# Ausgangsstufe.net
KiCad netlist of a schematic drawn in Altium Designer
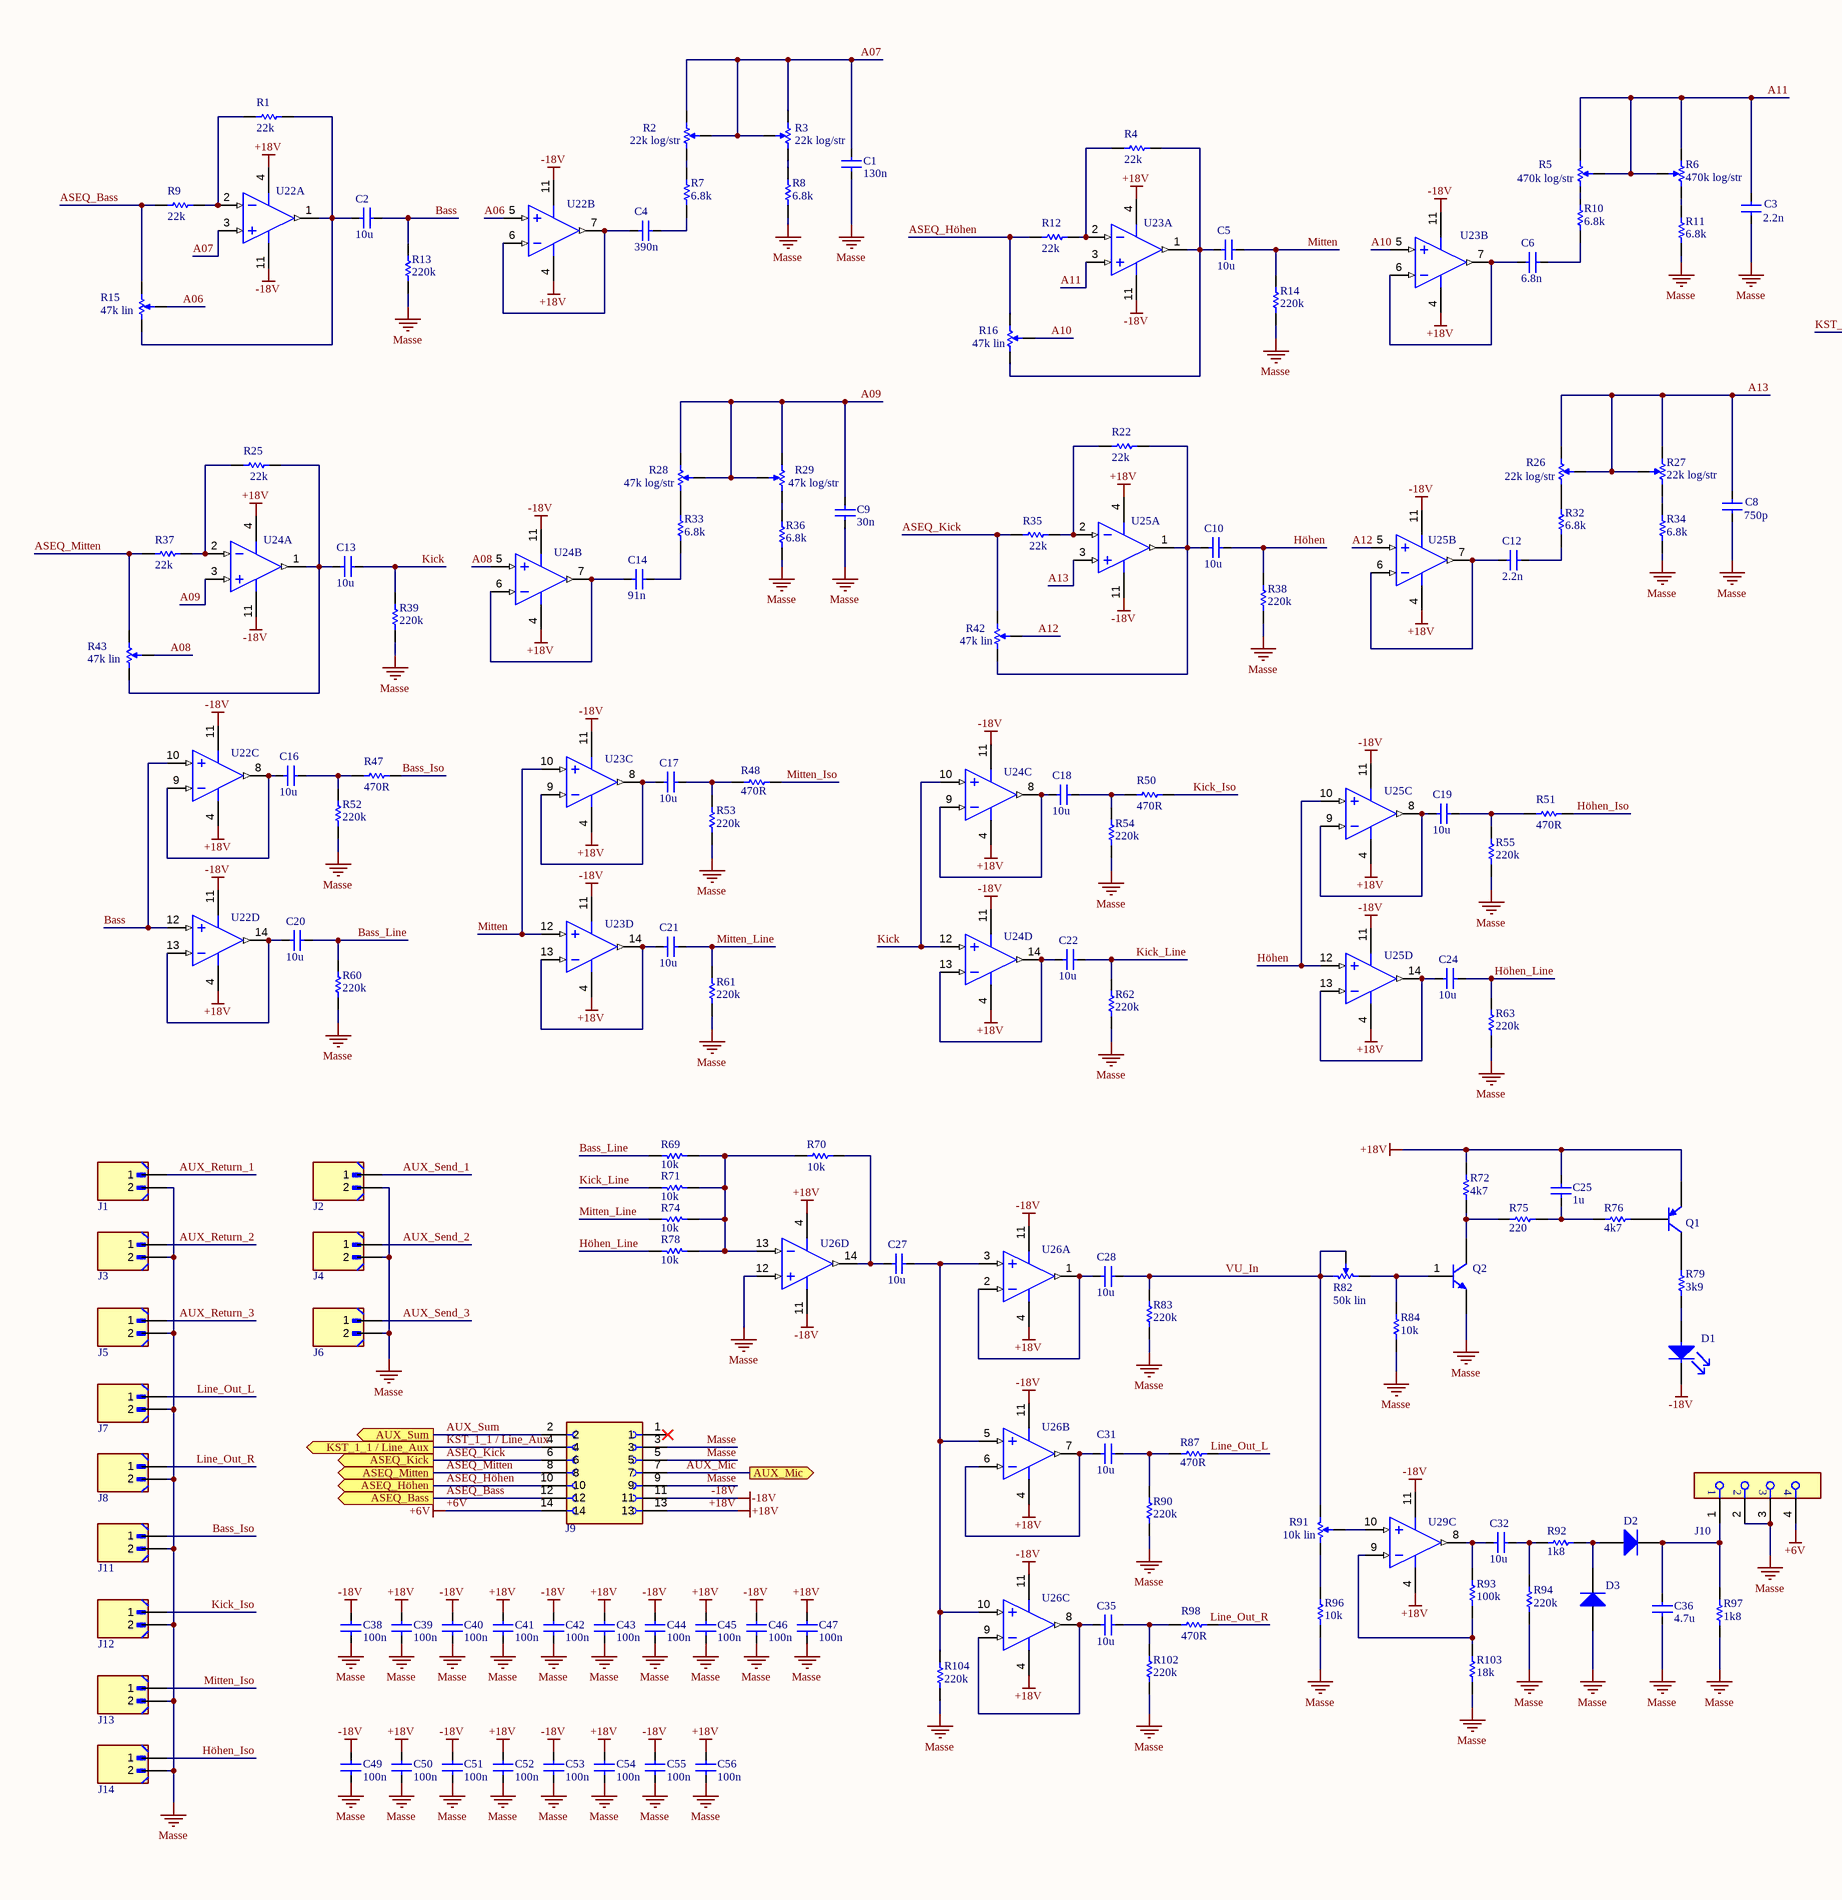
[diagram p0: Ausgangsstufe.SchDoc, left]
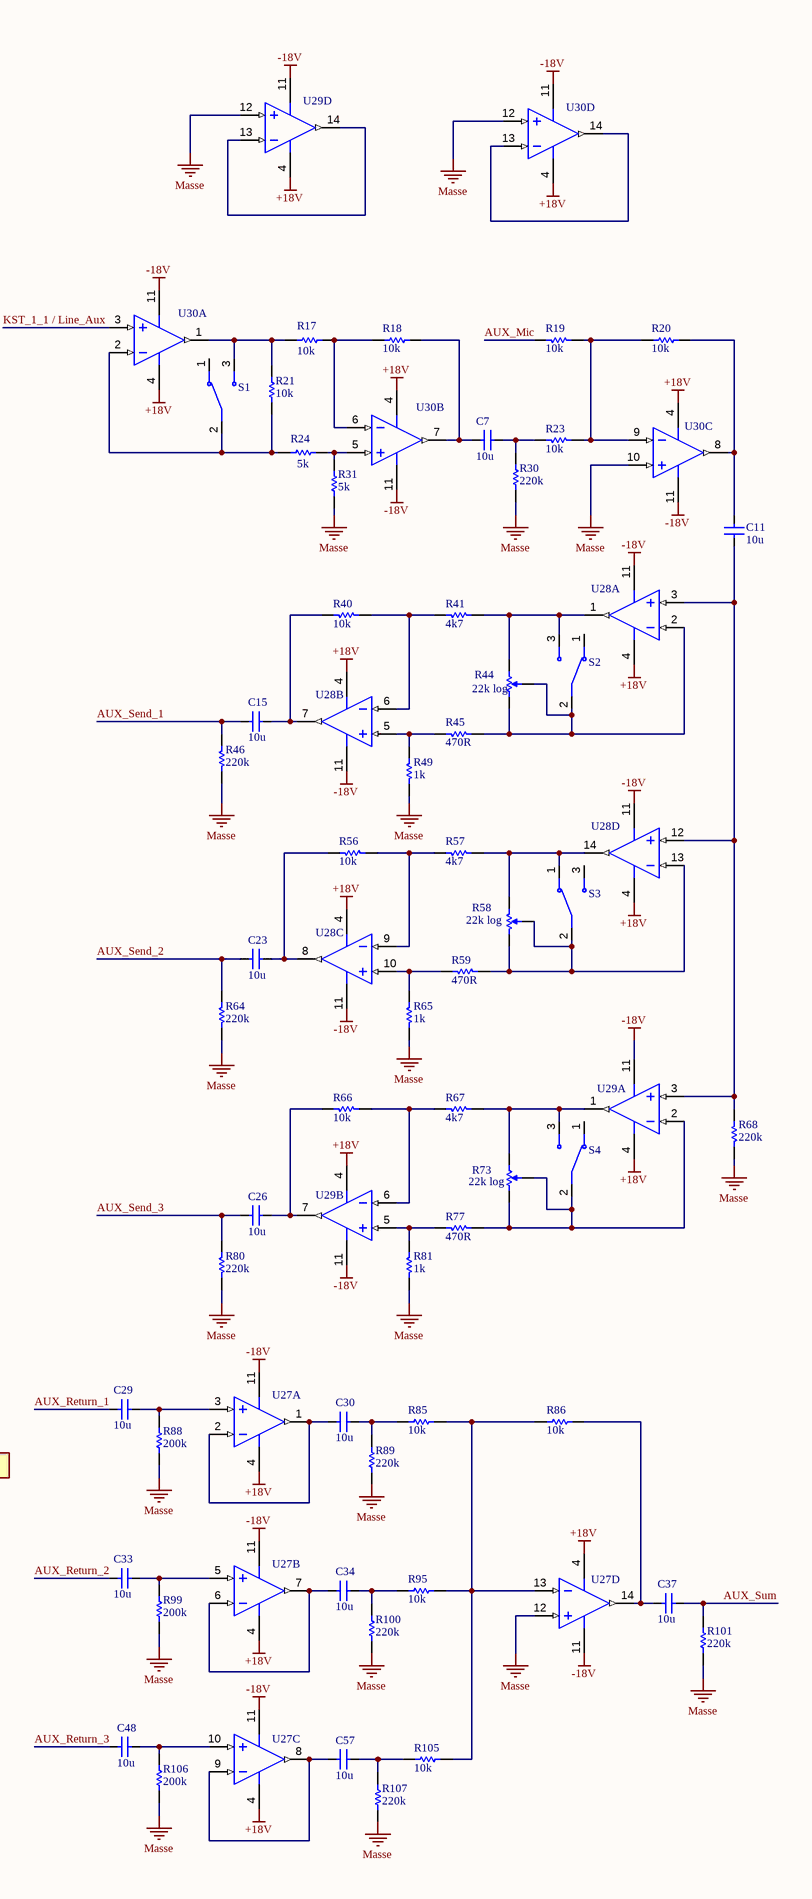
[diagram p1: Ausgangsstufe.SchDoc, right]

(export (version "E")
  (design (tool "Eeschema 10.0.6"))
  (components
    (comp (ref "C1")
      (value "130n")
      (footprint "0805")
      (description "0805 Kondensator")
      (libsource (lib "Bauteile") (part "0805 Kondensator"))
    )
    (comp (ref "C2")
      (value "10u")
      (footprint "0805")
      (description "0805 Kondensator")
      (libsource (lib "Bauteile") (part "0805 Kondensator"))
    )
    (comp (ref "C3")
      (value "2.2n")
      (footprint "0805")
      (description "0805 Kondensator")
      (libsource (lib "Bauteile") (part "0805 Kondensator"))
    )
    (comp (ref "C4")
      (value "390n")
      (footprint "0805")
      (description "0805 Kondensator")
      (libsource (lib "Bauteile") (part "0805 Kondensator"))
    )
    (comp (ref "C5")
      (value "10u")
      (footprint "0805")
      (description "0805 Kondensator")
      (libsource (lib "Bauteile") (part "0805 Kondensator"))
    )
    (comp (ref "C6")
      (value "6.8n")
      (footprint "0805")
      (description "0805 Kondensator")
      (libsource (lib "Bauteile") (part "0805 Kondensator"))
    )
    (comp (ref "C7")
      (value "10u")
      (footprint "0805")
      (description "0805 Kondensator")
      (libsource (lib "Bauteile") (part "0805 Kondensator"))
    )
    (comp (ref "C8")
      (value "750p")
      (footprint "0805")
      (description "0805 Kondensator")
      (libsource (lib "Bauteile") (part "0805 Kondensator"))
    )
    (comp (ref "C9")
      (value "30n")
      (footprint "0805")
      (description "0805 Kondensator")
      (libsource (lib "Bauteile") (part "0805 Kondensator"))
    )
    (comp (ref "C10")
      (value "10u")
      (footprint "0805")
      (description "0805 Kondensator")
      (libsource (lib "Bauteile") (part "0805 Kondensator"))
    )
    (comp (ref "C11")
      (value "10u")
      (footprint "0805")
      (description "0805 Kondensator")
      (libsource (lib "Bauteile") (part "0805 Kondensator"))
    )
    (comp (ref "C12")
      (value "2.2n")
      (footprint "0805")
      (description "0805 Kondensator")
      (libsource (lib "Bauteile") (part "0805 Kondensator"))
    )
    (comp (ref "C13")
      (value "10u")
      (footprint "0805")
      (description "0805 Kondensator")
      (libsource (lib "Bauteile") (part "0805 Kondensator"))
    )
    (comp (ref "C14")
      (value "91n")
      (footprint "0805")
      (description "0805 Kondensator")
      (libsource (lib "Bauteile") (part "0805 Kondensator"))
    )
    (comp (ref "C15")
      (value "10u")
      (footprint "0805")
      (description "0805 Kondensator")
      (libsource (lib "Bauteile") (part "0805 Kondensator"))
    )
    (comp (ref "C16")
      (value "10u")
      (footprint "0805")
      (description "0805 Kondensator")
      (libsource (lib "Bauteile") (part "0805 Kondensator"))
    )
    (comp (ref "C17")
      (value "10u")
      (footprint "0805")
      (description "0805 Kondensator")
      (libsource (lib "Bauteile") (part "0805 Kondensator"))
    )
    (comp (ref "C18")
      (value "10u")
      (footprint "0805")
      (description "0805 Kondensator")
      (libsource (lib "Bauteile") (part "0805 Kondensator"))
    )
    (comp (ref "C19")
      (value "10u")
      (footprint "0805")
      (description "0805 Kondensator")
      (libsource (lib "Bauteile") (part "0805 Kondensator"))
    )
    (comp (ref "C20")
      (value "10u")
      (footprint "0805")
      (description "0805 Kondensator")
      (libsource (lib "Bauteile") (part "0805 Kondensator"))
    )
    (comp (ref "C21")
      (value "10u")
      (footprint "0805")
      (description "0805 Kondensator")
      (libsource (lib "Bauteile") (part "0805 Kondensator"))
    )
    (comp (ref "C22")
      (value "10u")
      (footprint "0805")
      (description "0805 Kondensator")
      (libsource (lib "Bauteile") (part "0805 Kondensator"))
    )
    (comp (ref "C23")
      (value "10u")
      (footprint "0805")
      (description "0805 Kondensator")
      (libsource (lib "Bauteile") (part "0805 Kondensator"))
    )
    (comp (ref "C24")
      (value "10u")
      (footprint "0805")
      (description "0805 Kondensator")
      (libsource (lib "Bauteile") (part "0805 Kondensator"))
    )
    (comp (ref "C25")
      (value "1u")
      (footprint "0805")
      (description "0805 Kondensator")
      (libsource (lib "Bauteile") (part "0805 Kondensator"))
    )
    (comp (ref "C26")
      (value "10u")
      (footprint "0805")
      (description "0805 Kondensator")
      (libsource (lib "Bauteile") (part "0805 Kondensator"))
    )
    (comp (ref "C27")
      (value "10u")
      (footprint "0805")
      (description "0805 Kondensator")
      (libsource (lib "Bauteile") (part "0805 Kondensator"))
    )
    (comp (ref "C28")
      (value "10u")
      (footprint "0805")
      (description "0805 Kondensator")
      (libsource (lib "Bauteile") (part "0805 Kondensator"))
    )
    (comp (ref "C29")
      (value "10u")
      (footprint "0805")
      (description "0805 Kondensator")
      (libsource (lib "Bauteile") (part "0805 Kondensator"))
    )
    (comp (ref "C30")
      (value "10u")
      (footprint "0805")
      (description "0805 Kondensator")
      (libsource (lib "Bauteile") (part "0805 Kondensator"))
    )
    (comp (ref "C31")
      (value "10u")
      (footprint "0805")
      (description "0805 Kondensator")
      (libsource (lib "Bauteile") (part "0805 Kondensator"))
    )
    (comp (ref "C32")
      (value "10u")
      (footprint "0805")
      (description "0805 Kondensator")
      (libsource (lib "Bauteile") (part "0805 Kondensator"))
    )
    (comp (ref "C33")
      (value "10u")
      (footprint "0805")
      (description "0805 Kondensator")
      (libsource (lib "Bauteile") (part "0805 Kondensator"))
    )
    (comp (ref "C34")
      (value "10u")
      (footprint "0805")
      (description "0805 Kondensator")
      (libsource (lib "Bauteile") (part "0805 Kondensator"))
    )
    (comp (ref "C35")
      (value "10u")
      (footprint "0805")
      (description "0805 Kondensator")
      (libsource (lib "Bauteile") (part "0805 Kondensator"))
    )
    (comp (ref "C36")
      (value "4.7u")
      (footprint "0805")
      (description "0805 Kondensator")
      (libsource (lib "Bauteile") (part "0805 Kondensator"))
    )
    (comp (ref "C37")
      (value "10u")
      (footprint "0805")
      (description "0805 Kondensator")
      (libsource (lib "Bauteile") (part "0805 Kondensator"))
    )
    (comp (ref "C38")
      (value "100n")
      (footprint "0805")
      (description "0805 Kondensator")
      (libsource (lib "Bauteile") (part "0805 Kondensator"))
    )
    (comp (ref "C39")
      (value "100n")
      (footprint "0805")
      (description "0805 Kondensator")
      (libsource (lib "Bauteile") (part "0805 Kondensator"))
    )
    (comp (ref "C40")
      (value "100n")
      (footprint "0805")
      (description "0805 Kondensator")
      (libsource (lib "Bauteile") (part "0805 Kondensator"))
    )
    (comp (ref "C41")
      (value "100n")
      (footprint "0805")
      (description "0805 Kondensator")
      (libsource (lib "Bauteile") (part "0805 Kondensator"))
    )
    (comp (ref "C42")
      (value "100n")
      (footprint "0805")
      (description "0805 Kondensator")
      (libsource (lib "Bauteile") (part "0805 Kondensator"))
    )
    (comp (ref "C43")
      (value "100n")
      (footprint "0805")
      (description "0805 Kondensator")
      (libsource (lib "Bauteile") (part "0805 Kondensator"))
    )
    (comp (ref "C44")
      (value "100n")
      (footprint "0805")
      (description "0805 Kondensator")
      (libsource (lib "Bauteile") (part "0805 Kondensator"))
    )
    (comp (ref "C45")
      (value "100n")
      (footprint "0805")
      (description "0805 Kondensator")
      (libsource (lib "Bauteile") (part "0805 Kondensator"))
    )
    (comp (ref "C46")
      (value "100n")
      (footprint "0805")
      (description "0805 Kondensator")
      (libsource (lib "Bauteile") (part "0805 Kondensator"))
    )
    (comp (ref "C47")
      (value "100n")
      (footprint "0805")
      (description "0805 Kondensator")
      (libsource (lib "Bauteile") (part "0805 Kondensator"))
    )
    (comp (ref "C48")
      (value "10u")
      (footprint "0805")
      (description "0805 Kondensator")
      (libsource (lib "Bauteile") (part "0805 Kondensator"))
    )
    (comp (ref "C49")
      (value "100n")
      (footprint "0805")
      (description "0805 Kondensator")
      (libsource (lib "Bauteile") (part "0805 Kondensator"))
    )
    (comp (ref "C50")
      (value "100n")
      (footprint "0805")
      (description "0805 Kondensator")
      (libsource (lib "Bauteile") (part "0805 Kondensator"))
    )
    (comp (ref "C51")
      (value "100n")
      (footprint "0805")
      (description "0805 Kondensator")
      (libsource (lib "Bauteile") (part "0805 Kondensator"))
    )
    (comp (ref "C52")
      (value "100n")
      (footprint "0805")
      (description "0805 Kondensator")
      (libsource (lib "Bauteile") (part "0805 Kondensator"))
    )
    (comp (ref "C53")
      (value "100n")
      (footprint "0805")
      (description "0805 Kondensator")
      (libsource (lib "Bauteile") (part "0805 Kondensator"))
    )
    (comp (ref "C54")
      (value "100n")
      (footprint "0805")
      (description "0805 Kondensator")
      (libsource (lib "Bauteile") (part "0805 Kondensator"))
    )
    (comp (ref "C55")
      (value "100n")
      (footprint "0805")
      (description "0805 Kondensator")
      (libsource (lib "Bauteile") (part "0805 Kondensator"))
    )
    (comp (ref "C56")
      (value "100n")
      (footprint "0805")
      (description "0805 Kondensator")
      (libsource (lib "Bauteile") (part "0805 Kondensator"))
    )
    (comp (ref "C57")
      (value "10u")
      (footprint "0805")
      (description "0805 Kondensator")
      (libsource (lib "Bauteile") (part "0805 Kondensator"))
    )
    (comp (ref "D1")
      (value "WP710A10LGD")
      (footprint "Connector x2")
      (libsource (lib "Bauteile") (part "LED Buchsenleiste"))
    )
    (comp (ref "D2")
      (value "1N4148WS-7-F")
      (footprint "1N4148 Diode")
      (description "Fast Switching Diode, 75 V, 0.3 A, -65 to 150 degC, 2-Pin SOD323, RoHS, Tape and Reel")
      (libsource (lib "Bauteile") (part "1N4148 Diode"))
    )
    (comp (ref "D3")
      (value "1N4148WS-7-F")
      (footprint "1N4148 Diode")
      (description "Fast Switching Diode, 75 V, 0.3 A, -65 to 150 degC, 2-Pin SOD323, RoHS, Tape and Reel")
      (libsource (lib "Bauteile") (part "1N4148 Diode"))
    )
    (comp (ref "J1")
      (value "Connector x2")
      (footprint "Connector x2")
      (description "Connector Header Through Hole 2 position 0.100 (2.54mm)")
      (fields (field (name "MF") "Wurth Elektronik") (field (name "MP") "61300211121"))
      (libsource (lib "Bauteile") (part "Connector x2"))
    )
    (comp (ref "J2")
      (value "Connector x2")
      (footprint "Connector x2")
      (description "Connector Header Through Hole 2 position 0.100 (2.54mm)")
      (fields (field (name "MF") "Wurth Elektronik") (field (name "MP") "61300211121"))
      (libsource (lib "Bauteile") (part "Connector x2"))
    )
    (comp (ref "J3")
      (value "Connector x2")
      (footprint "Connector x2")
      (description "Connector Header Through Hole 2 position 0.100 (2.54mm)")
      (fields (field (name "MF") "Wurth Elektronik") (field (name "MP") "61300211121"))
      (libsource (lib "Bauteile") (part "Connector x2"))
    )
    (comp (ref "J4")
      (value "Connector x2")
      (footprint "Connector x2")
      (description "Connector Header Through Hole 2 position 0.100 (2.54mm)")
      (fields (field (name "MF") "Wurth Elektronik") (field (name "MP") "61300211121"))
      (libsource (lib "Bauteile") (part "Connector x2"))
    )
    (comp (ref "J5")
      (value "Connector x2")
      (footprint "Connector x2")
      (description "Connector Header Through Hole 2 position 0.100 (2.54mm)")
      (fields (field (name "MF") "Wurth Elektronik") (field (name "MP") "61300211121"))
      (libsource (lib "Bauteile") (part "Connector x2"))
    )
    (comp (ref "J6")
      (value "Connector x2")
      (footprint "Connector x2")
      (description "Connector Header Through Hole 2 position 0.100 (2.54mm)")
      (fields (field (name "MF") "Wurth Elektronik") (field (name "MP") "61300211121"))
      (libsource (lib "Bauteile") (part "Connector x2"))
    )
    (comp (ref "J7")
      (value "Connector x2")
      (footprint "Connector x2")
      (description "Connector Header Through Hole 2 position 0.100 (2.54mm)")
      (fields (field (name "MF") "Wurth Elektronik") (field (name "MP") "61300211121"))
      (libsource (lib "Bauteile") (part "Connector x2"))
    )
    (comp (ref "J8")
      (value "Connector x2")
      (footprint "Connector x2")
      (description "Connector Header Through Hole 2 position 0.100 (2.54mm)")
      (fields (field (name "MF") "Wurth Elektronik") (field (name "MP") "61300211121"))
      (libsource (lib "Bauteile") (part "Connector x2"))
    )
    (comp (ref "J9")
      (value "Connector x14")
      (footprint "Connector x14")
      (description "14 Position Header Connector Through Hole")
      (fields (field (name "MF") "Sullins Connector") (field (name "MP") "SFH11-PBPC-D07-ST-BK"))
      (libsource (lib "Bauteile") (part "Connector x14"))
    )
    (comp (ref "J10")
      (value "VU Meter")
      (footprint "Connector x4")
      (description "CONN RCPT 4POS 0.1 GOLD PCB")
      (libsource (lib "Bauteile") (part "Connector x4"))
    )
    (comp (ref "J11")
      (value "Connector x2")
      (footprint "Connector x2")
      (description "Connector Header Through Hole 2 position 0.100 (2.54mm)")
      (fields (field (name "MF") "Wurth Elektronik") (field (name "MP") "61300211121"))
      (libsource (lib "Bauteile") (part "Connector x2"))
    )
    (comp (ref "J12")
      (value "Connector x2")
      (footprint "Connector x2")
      (description "Connector Header Through Hole 2 position 0.100 (2.54mm)")
      (fields (field (name "MF") "Wurth Elektronik") (field (name "MP") "61300211121"))
      (libsource (lib "Bauteile") (part "Connector x2"))
    )
    (comp (ref "J13")
      (value "Connector x2")
      (footprint "Connector x2")
      (description "Connector Header Through Hole 2 position 0.100 (2.54mm)")
      (fields (field (name "MF") "Wurth Elektronik") (field (name "MP") "61300211121"))
      (libsource (lib "Bauteile") (part "Connector x2"))
    )
    (comp (ref "J14")
      (value "Connector x2")
      (footprint "Connector x2")
      (description "Connector Header Through Hole 2 position 0.100 (2.54mm)")
      (fields (field (name "MF") "Wurth Elektronik") (field (name "MP") "61300211121"))
      (libsource (lib "Bauteile") (part "Connector x2"))
    )
    (comp (ref "Q1")
      (value "BC807-40LT1G")
      (footprint "SOT23 Transistor")
      (description "General Purpose Transistor, PNP Silicon, 3-Pin SOT-23, Pb-Free, Tape and Reel")
      (fields (field (name "MANUFACTURER") "On Semiconductor"))
      (libsource (lib "Bauteile") (part "SOT23 BC807 PNP"))
    )
    (comp (ref "Q2")
      (value "BC817-40,215")
      (footprint "SOT23 Transistor")
      (description "TRANS NPN 45V 0.5A SOT23")
      (fields
        (field (name "OCTOPART") "https://octopart.com/bc817-40%2C215-nexperia-78739081")
        (field (name "MANUFACTURER") "Nexperia")
      )
      (libsource (lib "Bauteile") (part "SOT23 BC817 NPN"))
    )
    (comp (ref "R1")
      (value "22k")
      (footprint "0805")
      (description "0805 Widerstand")
      (libsource (lib "Bauteile") (part "0805 Widerstand"))
    )
    (comp (ref "R2")
      (value "22k log/str")
      (footprint "Connector x3")
      (description "Potentiometer")
      (libsource (lib "Bauteile") (part "Potentiometer Buchsenleiste"))
    )
    (comp (ref "R3")
      (value "22k log/str")
      (footprint "Connector x3")
      (description "Potentiometer")
      (libsource (lib "Bauteile") (part "Potentiometer Buchsenleiste"))
    )
    (comp (ref "R4")
      (value "22k")
      (footprint "0805")
      (description "0805 Widerstand")
      (libsource (lib "Bauteile") (part "0805 Widerstand"))
    )
    (comp (ref "R5")
      (value "470k log/str")
      (footprint "Connector x3")
      (description "Potentiometer")
      (libsource (lib "Bauteile") (part "Potentiometer Buchsenleiste"))
    )
    (comp (ref "R6")
      (value "470k log/str")
      (footprint "Connector x3")
      (description "Potentiometer")
      (libsource (lib "Bauteile") (part "Potentiometer Buchsenleiste"))
    )
    (comp (ref "R7")
      (value "6.8k")
      (footprint "0805")
      (description "0805 Widerstand")
      (libsource (lib "Bauteile") (part "0805 Widerstand"))
    )
    (comp (ref "R8")
      (value "6.8k")
      (footprint "0805")
      (description "0805 Widerstand")
      (libsource (lib "Bauteile") (part "0805 Widerstand"))
    )
    (comp (ref "R9")
      (value "22k")
      (footprint "0805")
      (description "0805 Widerstand")
      (libsource (lib "Bauteile") (part "0805 Widerstand"))
    )
    (comp (ref "R10")
      (value "6.8k")
      (footprint "0805")
      (description "0805 Widerstand")
      (libsource (lib "Bauteile") (part "0805 Widerstand"))
    )
    (comp (ref "R11")
      (value "6.8k")
      (footprint "0805")
      (description "0805 Widerstand")
      (libsource (lib "Bauteile") (part "0805 Widerstand"))
    )
    (comp (ref "R12")
      (value "22k")
      (footprint "0805")
      (description "0805 Widerstand")
      (libsource (lib "Bauteile") (part "0805 Widerstand"))
    )
    (comp (ref "R13")
      (value "220k")
      (footprint "0805")
      (description "0805 Widerstand")
      (libsource (lib "Bauteile") (part "0805 Widerstand"))
    )
    (comp (ref "R14")
      (value "220k")
      (footprint "0805")
      (description "0805 Widerstand")
      (libsource (lib "Bauteile") (part "0805 Widerstand"))
    )
    (comp (ref "R15")
      (value "47k lin")
      (footprint "Connector x3")
      (description "Potentiometer")
      (libsource (lib "Bauteile") (part "Potentiometer Buchsenleiste"))
    )
    (comp (ref "R16")
      (value "47k lin")
      (footprint "Connector x3")
      (description "Potentiometer")
      (libsource (lib "Bauteile") (part "Potentiometer Buchsenleiste"))
    )
    (comp (ref "R17")
      (value "10k")
      (footprint "0805")
      (description "0805 Widerstand")
      (libsource (lib "Bauteile") (part "0805 Widerstand"))
    )
    (comp (ref "R18")
      (value "10k")
      (footprint "0805")
      (description "0805 Widerstand")
      (libsource (lib "Bauteile") (part "0805 Widerstand"))
    )
    (comp (ref "R19")
      (value "10k")
      (footprint "0805")
      (description "0805 Widerstand")
      (libsource (lib "Bauteile") (part "0805 Widerstand"))
    )
    (comp (ref "R20")
      (value "10k")
      (footprint "0805")
      (description "0805 Widerstand")
      (libsource (lib "Bauteile") (part "0805 Widerstand"))
    )
    (comp (ref "R21")
      (value "10k")
      (footprint "0805")
      (description "0805 Widerstand")
      (libsource (lib "Bauteile") (part "0805 Widerstand"))
    )
    (comp (ref "R22")
      (value "22k")
      (footprint "0805")
      (description "0805 Widerstand")
      (libsource (lib "Bauteile") (part "0805 Widerstand"))
    )
    (comp (ref "R23")
      (value "10k")
      (footprint "0805")
      (description "0805 Widerstand")
      (libsource (lib "Bauteile") (part "0805 Widerstand"))
    )
    (comp (ref "R24")
      (value "5k")
      (footprint "0805")
      (description "0805 Widerstand")
      (libsource (lib "Bauteile") (part "0805 Widerstand"))
    )
    (comp (ref "R25")
      (value "22k")
      (footprint "0805")
      (description "0805 Widerstand")
      (libsource (lib "Bauteile") (part "0805 Widerstand"))
    )
    (comp (ref "R26")
      (value "22k log/str")
      (footprint "Connector x3")
      (description "Potentiometer")
      (libsource (lib "Bauteile") (part "Potentiometer Buchsenleiste"))
    )
    (comp (ref "R27")
      (value "22k log/str")
      (footprint "Connector x3")
      (description "Potentiometer")
      (libsource (lib "Bauteile") (part "Potentiometer Buchsenleiste"))
    )
    (comp (ref "R28")
      (value "47k log/str")
      (footprint "Connector x3")
      (description "Potentiometer")
      (libsource (lib "Bauteile") (part "Potentiometer Buchsenleiste"))
    )
    (comp (ref "R29")
      (value "47k log/str")
      (footprint "Connector x3")
      (description "Potentiometer")
      (libsource (lib "Bauteile") (part "Potentiometer Buchsenleiste"))
    )
    (comp (ref "R30")
      (value "220k")
      (footprint "0805")
      (description "0805 Widerstand")
      (libsource (lib "Bauteile") (part "0805 Widerstand"))
    )
    (comp (ref "R31")
      (value "5k")
      (footprint "0805")
      (description "0805 Widerstand")
      (libsource (lib "Bauteile") (part "0805 Widerstand"))
    )
    (comp (ref "R32")
      (value "6.8k")
      (footprint "0805")
      (description "0805 Widerstand")
      (libsource (lib "Bauteile") (part "0805 Widerstand"))
    )
    (comp (ref "R33")
      (value "6.8k")
      (footprint "0805")
      (description "0805 Widerstand")
      (libsource (lib "Bauteile") (part "0805 Widerstand"))
    )
    (comp (ref "R34")
      (value "6.8k")
      (footprint "0805")
      (description "0805 Widerstand")
      (libsource (lib "Bauteile") (part "0805 Widerstand"))
    )
    (comp (ref "R35")
      (value "22k")
      (footprint "0805")
      (description "0805 Widerstand")
      (libsource (lib "Bauteile") (part "0805 Widerstand"))
    )
    (comp (ref "R36")
      (value "6.8k")
      (footprint "0805")
      (description "0805 Widerstand")
      (libsource (lib "Bauteile") (part "0805 Widerstand"))
    )
    (comp (ref "R37")
      (value "22k")
      (footprint "0805")
      (description "0805 Widerstand")
      (libsource (lib "Bauteile") (part "0805 Widerstand"))
    )
    (comp (ref "R38")
      (value "220k")
      (footprint "0805")
      (description "0805 Widerstand")
      (libsource (lib "Bauteile") (part "0805 Widerstand"))
    )
    (comp (ref "R39")
      (value "220k")
      (footprint "0805")
      (description "0805 Widerstand")
      (libsource (lib "Bauteile") (part "0805 Widerstand"))
    )
    (comp (ref "R40")
      (value "10k")
      (footprint "0805")
      (description "0805 Widerstand")
      (libsource (lib "Bauteile") (part "0805 Widerstand"))
    )
    (comp (ref "R41")
      (value "4k7")
      (footprint "0805")
      (description "0805 Widerstand")
      (libsource (lib "Bauteile") (part "0805 Widerstand"))
    )
    (comp (ref "R42")
      (value "47k lin")
      (footprint "Connector x3")
      (description "Potentiometer")
      (libsource (lib "Bauteile") (part "Potentiometer Buchsenleiste"))
    )
    (comp (ref "R43")
      (value "47k lin")
      (footprint "Connector x3")
      (description "Potentiometer")
      (libsource (lib "Bauteile") (part "Potentiometer Buchsenleiste"))
    )
    (comp (ref "R44")
      (value "22k log")
      (footprint "Connector x3")
      (description "Potentiometer")
      (libsource (lib "Bauteile") (part "Potentiometer Buchsenleiste"))
    )
    (comp (ref "R45")
      (value "470R")
      (footprint "0805")
      (description "0805 Widerstand")
      (libsource (lib "Bauteile") (part "0805 Widerstand"))
    )
    (comp (ref "R46")
      (value "220k")
      (footprint "0805")
      (description "0805 Widerstand")
      (libsource (lib "Bauteile") (part "0805 Widerstand"))
    )
    (comp (ref "R47")
      (value "470R")
      (footprint "0805")
      (description "0805 Widerstand")
      (libsource (lib "Bauteile") (part "0805 Widerstand"))
    )
    (comp (ref "R48")
      (value "470R")
      (footprint "0805")
      (description "0805 Widerstand")
      (libsource (lib "Bauteile") (part "0805 Widerstand"))
    )
    (comp (ref "R49")
      (value "1k")
      (footprint "0805")
      (description "0805 Widerstand")
      (libsource (lib "Bauteile") (part "0805 Widerstand"))
    )
    (comp (ref "R50")
      (value "470R")
      (footprint "0805")
      (description "0805 Widerstand")
      (libsource (lib "Bauteile") (part "0805 Widerstand"))
    )
    (comp (ref "R51")
      (value "470R")
      (footprint "0805")
      (description "0805 Widerstand")
      (libsource (lib "Bauteile") (part "0805 Widerstand"))
    )
    (comp (ref "R52")
      (value "220k")
      (footprint "0805")
      (description "0805 Widerstand")
      (libsource (lib "Bauteile") (part "0805 Widerstand"))
    )
    (comp (ref "R53")
      (value "220k")
      (footprint "0805")
      (description "0805 Widerstand")
      (libsource (lib "Bauteile") (part "0805 Widerstand"))
    )
    (comp (ref "R54")
      (value "220k")
      (footprint "0805")
      (description "0805 Widerstand")
      (libsource (lib "Bauteile") (part "0805 Widerstand"))
    )
    (comp (ref "R55")
      (value "220k")
      (footprint "0805")
      (description "0805 Widerstand")
      (libsource (lib "Bauteile") (part "0805 Widerstand"))
    )
    (comp (ref "R56")
      (value "10k")
      (footprint "0805")
      (description "0805 Widerstand")
      (libsource (lib "Bauteile") (part "0805 Widerstand"))
    )
    (comp (ref "R57")
      (value "4k7")
      (footprint "0805")
      (description "0805 Widerstand")
      (libsource (lib "Bauteile") (part "0805 Widerstand"))
    )
    (comp (ref "R58")
      (value "22k log")
      (footprint "Connector x3")
      (description "Potentiometer")
      (libsource (lib "Bauteile") (part "Potentiometer Buchsenleiste"))
    )
    (comp (ref "R59")
      (value "470R")
      (footprint "0805")
      (description "0805 Widerstand")
      (libsource (lib "Bauteile") (part "0805 Widerstand"))
    )
    (comp (ref "R60")
      (value "220k")
      (footprint "0805")
      (description "0805 Widerstand")
      (libsource (lib "Bauteile") (part "0805 Widerstand"))
    )
    (comp (ref "R61")
      (value "220k")
      (footprint "0805")
      (description "0805 Widerstand")
      (libsource (lib "Bauteile") (part "0805 Widerstand"))
    )
    (comp (ref "R62")
      (value "220k")
      (footprint "0805")
      (description "0805 Widerstand")
      (libsource (lib "Bauteile") (part "0805 Widerstand"))
    )
    (comp (ref "R63")
      (value "220k")
      (footprint "0805")
      (description "0805 Widerstand")
      (libsource (lib "Bauteile") (part "0805 Widerstand"))
    )
    (comp (ref "R64")
      (value "220k")
      (footprint "0805")
      (description "0805 Widerstand")
      (libsource (lib "Bauteile") (part "0805 Widerstand"))
    )
    (comp (ref "R65")
      (value "1k")
      (footprint "0805")
      (description "0805 Widerstand")
      (libsource (lib "Bauteile") (part "0805 Widerstand"))
    )
    (comp (ref "R66")
      (value "10k")
      (footprint "0805")
      (description "0805 Widerstand")
      (libsource (lib "Bauteile") (part "0805 Widerstand"))
    )
    (comp (ref "R67")
      (value "4k7")
      (footprint "0805")
      (description "0805 Widerstand")
      (libsource (lib "Bauteile") (part "0805 Widerstand"))
    )
    (comp (ref "R68")
      (value "220k")
      (footprint "0805")
      (description "0805 Widerstand")
      (libsource (lib "Bauteile") (part "0805 Widerstand"))
    )
    (comp (ref "R69")
      (value "10k")
      (footprint "0805")
      (description "0805 Widerstand")
      (libsource (lib "Bauteile") (part "0805 Widerstand"))
    )
    (comp (ref "R70")
      (value "10k")
      (footprint "0805")
      (description "0805 Widerstand")
      (libsource (lib "Bauteile") (part "0805 Widerstand"))
    )
    (comp (ref "R71")
      (value "10k")
      (footprint "0805")
      (description "0805 Widerstand")
      (libsource (lib "Bauteile") (part "0805 Widerstand"))
    )
    (comp (ref "R72")
      (value "4k7")
      (footprint "0805")
      (description "0805 Widerstand")
      (libsource (lib "Bauteile") (part "0805 Widerstand"))
    )
    (comp (ref "R73")
      (value "22k log")
      (footprint "Connector x3")
      (description "Potentiometer")
      (libsource (lib "Bauteile") (part "Potentiometer Buchsenleiste"))
    )
    (comp (ref "R74")
      (value "10k")
      (footprint "0805")
      (description "0805 Widerstand")
      (libsource (lib "Bauteile") (part "0805 Widerstand"))
    )
    (comp (ref "R75")
      (value "220")
      (footprint "0805")
      (description "0805 Widerstand")
      (libsource (lib "Bauteile") (part "0805 Widerstand"))
    )
    (comp (ref "R76")
      (value "4k7")
      (footprint "0805")
      (description "0805 Widerstand")
      (libsource (lib "Bauteile") (part "0805 Widerstand"))
    )
    (comp (ref "R77")
      (value "470R")
      (footprint "0805")
      (description "0805 Widerstand")
      (libsource (lib "Bauteile") (part "0805 Widerstand"))
    )
    (comp (ref "R78")
      (value "10k")
      (footprint "0805")
      (description "0805 Widerstand")
      (libsource (lib "Bauteile") (part "0805 Widerstand"))
    )
    (comp (ref "R79")
      (value "3k9")
      (footprint "0805")
      (description "0805 Widerstand")
      (libsource (lib "Bauteile") (part "0805 Widerstand"))
    )
    (comp (ref "R80")
      (value "220k")
      (footprint "0805")
      (description "0805 Widerstand")
      (libsource (lib "Bauteile") (part "0805 Widerstand"))
    )
    (comp (ref "R81")
      (value "1k")
      (footprint "0805")
      (description "0805 Widerstand")
      (libsource (lib "Bauteile") (part "0805 Widerstand"))
    )
    (comp (ref "R82")
      (value "50k lin")
      (footprint "SMD Trimmer 3314G")
      (libsource (lib "Bauteile") (part "SMD Trimmer 3314G"))
    )
    (comp (ref "R83")
      (value "220k")
      (footprint "0805")
      (description "0805 Widerstand")
      (libsource (lib "Bauteile") (part "0805 Widerstand"))
    )
    (comp (ref "R84")
      (value "10k")
      (footprint "0805")
      (description "0805 Widerstand")
      (libsource (lib "Bauteile") (part "0805 Widerstand"))
    )
    (comp (ref "R85")
      (value "10k")
      (footprint "0805")
      (description "0805 Widerstand")
      (libsource (lib "Bauteile") (part "0805 Widerstand"))
    )
    (comp (ref "R86")
      (value "10k")
      (footprint "0805")
      (description "0805 Widerstand")
      (libsource (lib "Bauteile") (part "0805 Widerstand"))
    )
    (comp (ref "R87")
      (value "470R")
      (footprint "0805")
      (description "0805 Widerstand")
      (libsource (lib "Bauteile") (part "0805 Widerstand"))
    )
    (comp (ref "R88")
      (value "200k")
      (footprint "0805")
      (description "0805 Widerstand")
      (libsource (lib "Bauteile") (part "0805 Widerstand"))
    )
    (comp (ref "R89")
      (value "220k")
      (footprint "0805")
      (description "0805 Widerstand")
      (libsource (lib "Bauteile") (part "0805 Widerstand"))
    )
    (comp (ref "R90")
      (value "220k")
      (footprint "0805")
      (description "0805 Widerstand")
      (libsource (lib "Bauteile") (part "0805 Widerstand"))
    )
    (comp (ref "R91")
      (value "10k lin")
      (footprint "SMD Trimmer 3314G")
      (libsource (lib "Bauteile") (part "SMD Trimmer 3314G"))
    )
    (comp (ref "R92")
      (value "1k8")
      (footprint "0805")
      (description "0805 Widerstand")
      (libsource (lib "Bauteile") (part "0805 Widerstand"))
    )
    (comp (ref "R93")
      (value "100k")
      (footprint "0805")
      (description "0805 Widerstand")
      (libsource (lib "Bauteile") (part "0805 Widerstand"))
    )
    (comp (ref "R94")
      (value "220k")
      (footprint "0805")
      (description "0805 Widerstand")
      (libsource (lib "Bauteile") (part "0805 Widerstand"))
    )
    (comp (ref "R95")
      (value "10k")
      (footprint "0805")
      (description "0805 Widerstand")
      (libsource (lib "Bauteile") (part "0805 Widerstand"))
    )
    (comp (ref "R96")
      (value "10k")
      (footprint "0805")
      (description "0805 Widerstand")
      (libsource (lib "Bauteile") (part "0805 Widerstand"))
    )
    (comp (ref "R97")
      (value "1k8")
      (footprint "0805")
      (description "0805 Widerstand")
      (libsource (lib "Bauteile") (part "0805 Widerstand"))
    )
    (comp (ref "R98")
      (value "470R")
      (footprint "0805")
      (description "0805 Widerstand")
      (libsource (lib "Bauteile") (part "0805 Widerstand"))
    )
    (comp (ref "R99")
      (value "200k")
      (footprint "0805")
      (description "0805 Widerstand")
      (libsource (lib "Bauteile") (part "0805 Widerstand"))
    )
    (comp (ref "R100")
      (value "220k")
      (footprint "0805")
      (description "0805 Widerstand")
      (libsource (lib "Bauteile") (part "0805 Widerstand"))
    )
    (comp (ref "R101")
      (value "220k")
      (footprint "0805")
      (description "0805 Widerstand")
      (libsource (lib "Bauteile") (part "0805 Widerstand"))
    )
    (comp (ref "R102")
      (value "220k")
      (footprint "0805")
      (description "0805 Widerstand")
      (libsource (lib "Bauteile") (part "0805 Widerstand"))
    )
    (comp (ref "R103")
      (value "18k")
      (footprint "0805")
      (description "0805 Widerstand")
      (libsource (lib "Bauteile") (part "0805 Widerstand"))
    )
    (comp (ref "R104")
      (value "220k")
      (footprint "0805")
      (description "0805 Widerstand")
      (libsource (lib "Bauteile") (part "0805 Widerstand"))
    )
    (comp (ref "R105")
      (value "10k")
      (footprint "0805")
      (description "0805 Widerstand")
      (libsource (lib "Bauteile") (part "0805 Widerstand"))
    )
    (comp (ref "R106")
      (value "200k")
      (footprint "0805")
      (description "0805 Widerstand")
      (libsource (lib "Bauteile") (part "0805 Widerstand"))
    )
    (comp (ref "R107")
      (value "220k")
      (footprint "0805")
      (description "0805 Widerstand")
      (libsource (lib "Bauteile") (part "0805 Widerstand"))
    )
    (comp (ref "S1")
      (value "Schalter Buchsenleiste")
      (footprint "Connector x3")
      (description "Toggle Switch SPDT Through Hole")
      (fields (field (name "MP") "100SP1T1B4M2QE"))
      (libsource (lib "Bauteile") (part "Schalter Buchsenleiste"))
    )
    (comp (ref "S2")
      (value "Schalter Buchsenleiste")
      (footprint "Connector x3")
      (description "Toggle Switch SPDT Through Hole")
      (fields (field (name "MP") "100SP1T1B4M2QE"))
      (libsource (lib "Bauteile") (part "Schalter Buchsenleiste"))
    )
    (comp (ref "S3")
      (value "Schalter Buchsenleiste")
      (footprint "Connector x3")
      (description "Toggle Switch SPDT Through Hole")
      (fields (field (name "MP") "100SP1T1B4M2QE"))
      (libsource (lib "Bauteile") (part "Schalter Buchsenleiste"))
    )
    (comp (ref "S4")
      (value "Schalter Buchsenleiste")
      (footprint "Connector x3")
      (description "Toggle Switch SPDT Through Hole")
      (fields (field (name "MP") "100SP1T1B4M2QE"))
      (libsource (lib "Bauteile") (part "Schalter Buchsenleiste"))
    )
    (comp (ref "U22")
      (value "OPA4134UA")
      (footprint "DIP14 IC Socket")
      (fields (field (name "MANUFACTURER") "Texas Instruments"))
      (libsource (lib "Bauteile") (part "SOIC OPA4134UA"))
    )
    (comp (ref "U23")
      (value "OPA4134UA")
      (footprint "DIP14 IC Socket")
      (fields (field (name "MANUFACTURER") "Texas Instruments"))
      (libsource (lib "Bauteile") (part "SOIC OPA4134UA"))
    )
    (comp (ref "U24")
      (value "OPA4134UA")
      (footprint "DIP14 IC Socket")
      (fields (field (name "MANUFACTURER") "Texas Instruments"))
      (libsource (lib "Bauteile") (part "SOIC OPA4134UA"))
    )
    (comp (ref "U25")
      (value "OPA4134UA")
      (footprint "DIP14 IC Socket")
      (fields (field (name "MANUFACTURER") "Texas Instruments"))
      (libsource (lib "Bauteile") (part "SOIC OPA4134UA"))
    )
    (comp (ref "U26")
      (value "OPA4134UA")
      (footprint "DIP14 IC Socket")
      (fields (field (name "MANUFACTURER") "Texas Instruments"))
      (libsource (lib "Bauteile") (part "SOIC OPA4134UA"))
    )
    (comp (ref "U27")
      (value "OPA4134UA")
      (footprint "DIP14 IC Socket")
      (fields (field (name "MANUFACTURER") "Texas Instruments"))
      (libsource (lib "Bauteile") (part "SOIC OPA4134UA"))
    )
    (comp (ref "U28")
      (value "OPA4134UA")
      (footprint "DIP14 IC Socket")
      (fields (field (name "MANUFACTURER") "Texas Instruments"))
      (libsource (lib "Bauteile") (part "SOIC OPA4134UA"))
    )
    (comp (ref "U29")
      (value "OPA4134UA")
      (footprint "DIP14 IC Socket")
      (fields (field (name "MANUFACTURER") "Texas Instruments"))
      (libsource (lib "Bauteile") (part "SOIC OPA4134UA"))
    )
    (comp (ref "U30")
      (value "OPA4134UA")
      (footprint "DIP14 IC Socket")
      (fields (field (name "MANUFACTURER") "Texas Instruments"))
      (libsource (lib "Bauteile") (part "SOIC OPA4134UA"))
    )
  )
  (nets
    (net (code "1") (name "+6V") (class "Default")
      (node (ref "J10") (pin "4") (pinfunction "4_4") (pintype "passive"))
      (node (ref "J9") (pin "14") (pinfunction "14_14") (pintype "passive"))
    )
    (net (code "2") (name "+18V") (class "Default")
      (node (ref "C25") (pin "2") (pinfunction "2_2") (pintype "passive"))
      (node (ref "C39") (pin "2") (pinfunction "2_2") (pintype "passive"))
      (node (ref "C41") (pin "2") (pinfunction "2_2") (pintype "passive"))
      (node (ref "C43") (pin "2") (pinfunction "2_2") (pintype "passive"))
      (node (ref "C45") (pin "2") (pinfunction "2_2") (pintype "passive"))
      (node (ref "C47") (pin "2") (pinfunction "2_2") (pintype "passive"))
      (node (ref "C50") (pin "2") (pinfunction "2_2") (pintype "passive"))
      (node (ref "C52") (pin "2") (pinfunction "2_2") (pintype "passive"))
      (node (ref "C54") (pin "2") (pinfunction "2_2") (pintype "passive"))
      (node (ref "C56") (pin "2") (pinfunction "2_2") (pintype "passive"))
      (node (ref "J9") (pin "13") (pinfunction "13_13") (pintype "passive"))
      (node (ref "Q1") (pin "2") (pinfunction "E_2") (pintype "passive"))
      (node (ref "R72") (pin "2") (pinfunction "2_2") (pintype "passive"))
      (node (ref "U22") (pin "4") (pinfunction "V+_4") (pintype "power_in"))
      (node (ref "U23") (pin "4") (pinfunction "V+_4") (pintype "power_in"))
      (node (ref "U24") (pin "4") (pinfunction "V+_4") (pintype "power_in"))
      (node (ref "U25") (pin "4") (pinfunction "V+_4") (pintype "power_in"))
      (node (ref "U26") (pin "4") (pinfunction "V+_4") (pintype "power_in"))
      (node (ref "U27") (pin "4") (pinfunction "V+_4") (pintype "power_in"))
      (node (ref "U28") (pin "4") (pinfunction "V+_4") (pintype "power_in"))
      (node (ref "U29") (pin "4") (pinfunction "V+_4") (pintype "power_in"))
      (node (ref "U30") (pin "4") (pinfunction "V+_4") (pintype "power_in"))
    )
    (net (code "3") (name "-18V") (class "Default")
      (node (ref "C38") (pin "2") (pinfunction "2_2") (pintype "passive"))
      (node (ref "C40") (pin "2") (pinfunction "2_2") (pintype "passive"))
      (node (ref "C42") (pin "2") (pinfunction "2_2") (pintype "passive"))
      (node (ref "C44") (pin "2") (pinfunction "2_2") (pintype "passive"))
      (node (ref "C46") (pin "2") (pinfunction "2_2") (pintype "passive"))
      (node (ref "C49") (pin "2") (pinfunction "2_2") (pintype "passive"))
      (node (ref "C51") (pin "2") (pinfunction "2_2") (pintype "passive"))
      (node (ref "C53") (pin "2") (pinfunction "2_2") (pintype "passive"))
      (node (ref "C55") (pin "2") (pinfunction "2_2") (pintype "passive"))
      (node (ref "D1") (pin "2") (pinfunction "K_2") (pintype "passive"))
      (node (ref "J9") (pin "11") (pinfunction "11_11") (pintype "passive"))
      (node (ref "U22") (pin "11") (pinfunction "V-_11") (pintype "power_in"))
      (node (ref "U23") (pin "11") (pinfunction "V-_11") (pintype "power_in"))
      (node (ref "U24") (pin "11") (pinfunction "V-_11") (pintype "power_in"))
      (node (ref "U25") (pin "11") (pinfunction "V-_11") (pintype "power_in"))
      (node (ref "U26") (pin "11") (pinfunction "V-_11") (pintype "power_in"))
      (node (ref "U27") (pin "11") (pinfunction "V-_11") (pintype "power_in"))
      (node (ref "U28") (pin "11") (pinfunction "V-_11") (pintype "power_in"))
      (node (ref "U29") (pin "11") (pinfunction "V-_11") (pintype "power_in"))
      (node (ref "U30") (pin "11") (pinfunction "V-_11") (pintype "power_in"))
    )
    (net (code "4") (name "/A06") (class "Default")
      (node (ref "R15") (pin "2") (pinfunction "2_2") (pintype "passive"))
      (node (ref "U22") (pin "5") (pinfunction "IN_B+_5") (pintype "input"))
    )
    (net (code "5") (name "/A07") (class "Default")
      (node (ref "C1") (pin "2") (pinfunction "2_2") (pintype "passive"))
      (node (ref "R2") (pin "2") (pinfunction "2_2") (pintype "passive"))
      (node (ref "R2") (pin "3") (pinfunction "3_3") (pintype "passive"))
      (node (ref "R3") (pin "1") (pinfunction "1_1") (pintype "passive"))
      (node (ref "R3") (pin "2") (pinfunction "2_2") (pintype "passive"))
      (node (ref "U22") (pin "3") (pinfunction "IN_A+_3") (pintype "input"))
    )
    (net (code "6") (name "/A08") (class "Default")
      (node (ref "R43") (pin "2") (pinfunction "2_2") (pintype "passive"))
      (node (ref "U24") (pin "5") (pinfunction "IN_B+_5") (pintype "input"))
    )
    (net (code "7") (name "/A09") (class "Default")
      (node (ref "C9") (pin "2") (pinfunction "2_2") (pintype "passive"))
      (node (ref "R28") (pin "2") (pinfunction "2_2") (pintype "passive"))
      (node (ref "R28") (pin "3") (pinfunction "3_3") (pintype "passive"))
      (node (ref "R29") (pin "1") (pinfunction "1_1") (pintype "passive"))
      (node (ref "R29") (pin "2") (pinfunction "2_2") (pintype "passive"))
      (node (ref "U24") (pin "3") (pinfunction "IN_A+_3") (pintype "input"))
    )
    (net (code "8") (name "/A10") (class "Default")
      (node (ref "R16") (pin "2") (pinfunction "2_2") (pintype "passive"))
      (node (ref "U23") (pin "5") (pinfunction "IN_B+_5") (pintype "input"))
    )
    (net (code "9") (name "/A11") (class "Default")
      (node (ref "C3") (pin "2") (pinfunction "2_2") (pintype "passive"))
      (node (ref "R5") (pin "2") (pinfunction "2_2") (pintype "passive"))
      (node (ref "R5") (pin "3") (pinfunction "3_3") (pintype "passive"))
      (node (ref "R6") (pin "1") (pinfunction "1_1") (pintype "passive"))
      (node (ref "R6") (pin "2") (pinfunction "2_2") (pintype "passive"))
      (node (ref "U23") (pin "3") (pinfunction "IN_A+_3") (pintype "input"))
    )
    (net (code "10") (name "/A12") (class "Default")
      (node (ref "R42") (pin "2") (pinfunction "2_2") (pintype "passive"))
      (node (ref "U25") (pin "5") (pinfunction "IN_B+_5") (pintype "input"))
    )
    (net (code "11") (name "/A13") (class "Default")
      (node (ref "C8") (pin "2") (pinfunction "2_2") (pintype "passive"))
      (node (ref "R26") (pin "2") (pinfunction "2_2") (pintype "passive"))
      (node (ref "R26") (pin "3") (pinfunction "3_3") (pintype "passive"))
      (node (ref "R27") (pin "1") (pinfunction "1_1") (pintype "passive"))
      (node (ref "R27") (pin "2") (pinfunction "2_2") (pintype "passive"))
      (node (ref "U25") (pin "3") (pinfunction "IN_A+_3") (pintype "input"))
    )
    (net (code "12") (name "/ASEQ_Bass") (class "Default")
      (node (ref "J9") (pin "12") (pinfunction "12_12") (pintype "passive"))
      (node (ref "R15") (pin "3") (pinfunction "3_3") (pintype "passive"))
      (node (ref "R9") (pin "1") (pinfunction "1_1") (pintype "passive"))
    )
    (net (code "13") (name "/ASEQ_Höhen") (class "Default")
      (node (ref "J9") (pin "10") (pinfunction "10_10") (pintype "passive"))
      (node (ref "R12") (pin "1") (pinfunction "1_1") (pintype "passive"))
      (node (ref "R16") (pin "3") (pinfunction "3_3") (pintype "passive"))
    )
    (net (code "14") (name "/ASEQ_Kick") (class "Default")
      (node (ref "J9") (pin "6") (pinfunction "6_6") (pintype "passive"))
      (node (ref "R35") (pin "1") (pinfunction "1_1") (pintype "passive"))
      (node (ref "R42") (pin "3") (pinfunction "3_3") (pintype "passive"))
    )
    (net (code "15") (name "/ASEQ_Mitten") (class "Default")
      (node (ref "J9") (pin "8") (pinfunction "8_8") (pintype "passive"))
      (node (ref "R37") (pin "1") (pinfunction "1_1") (pintype "passive"))
      (node (ref "R43") (pin "3") (pinfunction "3_3") (pintype "passive"))
    )
    (net (code "16") (name "/AUX_Mic") (class "Default")
      (node (ref "J9") (pin "7") (pinfunction "7_7") (pintype "passive"))
      (node (ref "R19") (pin "2") (pinfunction "2_2") (pintype "passive"))
    )
    (net (code "17") (name "/AUX_Return_1") (class "Default")
      (node (ref "C29") (pin "1") (pinfunction "1_1") (pintype "passive"))
      (node (ref "J1") (pin "1") (pinfunction "1_1") (pintype "passive"))
    )
    (net (code "18") (name "/AUX_Return_2") (class "Default")
      (node (ref "C33") (pin "1") (pinfunction "1_1") (pintype "passive"))
      (node (ref "J3") (pin "1") (pinfunction "1_1") (pintype "passive"))
    )
    (net (code "19") (name "/AUX_Return_3") (class "Default")
      (node (ref "C48") (pin "2") (pinfunction "2_2") (pintype "passive"))
      (node (ref "J5") (pin "1") (pinfunction "1_1") (pintype "passive"))
    )
    (net (code "20") (name "/AUX_Send_1") (class "Default")
      (node (ref "C15") (pin "2") (pinfunction "2_2") (pintype "passive"))
      (node (ref "J2") (pin "1") (pinfunction "1_1") (pintype "passive"))
      (node (ref "R46") (pin "2") (pinfunction "2_2") (pintype "passive"))
    )
    (net (code "21") (name "/AUX_Send_2") (class "Default")
      (node (ref "C23") (pin "2") (pinfunction "2_2") (pintype "passive"))
      (node (ref "J4") (pin "1") (pinfunction "1_1") (pintype "passive"))
      (node (ref "R64") (pin "2") (pinfunction "2_2") (pintype "passive"))
    )
    (net (code "22") (name "/AUX_Send_3") (class "Default")
      (node (ref "C26") (pin "2") (pinfunction "2_2") (pintype "passive"))
      (node (ref "J6") (pin "1") (pinfunction "1_1") (pintype "passive"))
      (node (ref "R80") (pin "2") (pinfunction "2_2") (pintype "passive"))
    )
    (net (code "23") (name "/AUX_Sum") (class "Default")
      (node (ref "C37") (pin "2") (pinfunction "2_2") (pintype "passive"))
      (node (ref "J9") (pin "2") (pinfunction "2_2") (pintype "passive"))
      (node (ref "R101") (pin "2") (pinfunction "2_2") (pintype "passive"))
    )
    (net (code "24") (name "/Bass") (class "Default")
      (node (ref "C2") (pin "2") (pinfunction "2_2") (pintype "passive"))
      (node (ref "R13") (pin "2") (pinfunction "2_2") (pintype "passive"))
      (node (ref "U22") (pin "10") (pinfunction "IN_C+_10") (pintype "input"))
      (node (ref "U22") (pin "12") (pinfunction "IN_D+_12") (pintype "input"))
    )
    (net (code "25") (name "/Bass_Iso") (class "Default")
      (node (ref "J11") (pin "1") (pinfunction "1_1") (pintype "passive"))
      (node (ref "R47") (pin "2") (pinfunction "2_2") (pintype "passive"))
    )
    (net (code "26") (name "/Bass_Line") (class "Default")
      (node (ref "C20") (pin "2") (pinfunction "2_2") (pintype "passive"))
      (node (ref "R60") (pin "2") (pinfunction "2_2") (pintype "passive"))
      (node (ref "R69") (pin "1") (pinfunction "1_1") (pintype "passive"))
    )
    (net (code "27") (name "/Höhen") (class "Default")
      (node (ref "C10") (pin "2") (pinfunction "2_2") (pintype "passive"))
      (node (ref "R38") (pin "2") (pinfunction "2_2") (pintype "passive"))
      (node (ref "U25") (pin "10") (pinfunction "IN_C+_10") (pintype "input"))
      (node (ref "U25") (pin "12") (pinfunction "IN_D+_12") (pintype "input"))
    )
    (net (code "28") (name "/Höhen_Iso") (class "Default")
      (node (ref "J14") (pin "1") (pinfunction "1_1") (pintype "passive"))
      (node (ref "R51") (pin "2") (pinfunction "2_2") (pintype "passive"))
    )
    (net (code "29") (name "/Höhen_Line") (class "Default")
      (node (ref "C24") (pin "2") (pinfunction "2_2") (pintype "passive"))
      (node (ref "R63") (pin "2") (pinfunction "2_2") (pintype "passive"))
      (node (ref "R78") (pin "1") (pinfunction "1_1") (pintype "passive"))
    )
    (net (code "30") (name "/KST_1_1 {slash} Line_Aux") (class "Default")
      (node (ref "J9") (pin "4") (pinfunction "4_4") (pintype "passive"))
      (node (ref "U30") (pin "3") (pinfunction "IN_A+_3") (pintype "input"))
    )
    (net (code "31") (name "/Kick") (class "Default")
      (node (ref "C13") (pin "2") (pinfunction "2_2") (pintype "passive"))
      (node (ref "R39") (pin "2") (pinfunction "2_2") (pintype "passive"))
      (node (ref "U24") (pin "10") (pinfunction "IN_C+_10") (pintype "input"))
      (node (ref "U24") (pin "12") (pinfunction "IN_D+_12") (pintype "input"))
    )
    (net (code "32") (name "/Kick_Iso") (class "Default")
      (node (ref "J12") (pin "1") (pinfunction "1_1") (pintype "passive"))
      (node (ref "R50") (pin "2") (pinfunction "2_2") (pintype "passive"))
    )
    (net (code "33") (name "/Kick_Line") (class "Default")
      (node (ref "C22") (pin "2") (pinfunction "2_2") (pintype "passive"))
      (node (ref "R62") (pin "2") (pinfunction "2_2") (pintype "passive"))
      (node (ref "R71") (pin "1") (pinfunction "1_1") (pintype "passive"))
    )
    (net (code "34") (name "/Line_Out_L") (class "Default")
      (node (ref "J7") (pin "1") (pinfunction "1_1") (pintype "passive"))
      (node (ref "R87") (pin "2") (pinfunction "2_2") (pintype "passive"))
    )
    (net (code "35") (name "/Line_Out_R") (class "Default")
      (node (ref "J8") (pin "1") (pinfunction "1_1") (pintype "passive"))
      (node (ref "R98") (pin "2") (pinfunction "2_2") (pintype "passive"))
    )
    (net (code "36") (name "/Mitten") (class "Default")
      (node (ref "C5") (pin "2") (pinfunction "2_2") (pintype "passive"))
      (node (ref "R14") (pin "2") (pinfunction "2_2") (pintype "passive"))
      (node (ref "U23") (pin "10") (pinfunction "IN_C+_10") (pintype "input"))
      (node (ref "U23") (pin "12") (pinfunction "IN_D+_12") (pintype "input"))
    )
    (net (code "37") (name "/Mitten_Iso") (class "Default")
      (node (ref "J13") (pin "1") (pinfunction "1_1") (pintype "passive"))
      (node (ref "R48") (pin "2") (pinfunction "2_2") (pintype "passive"))
    )
    (net (code "38") (name "/Mitten_Line") (class "Default")
      (node (ref "C21") (pin "2") (pinfunction "2_2") (pintype "passive"))
      (node (ref "R61") (pin "2") (pinfunction "2_2") (pintype "passive"))
      (node (ref "R74") (pin "1") (pinfunction "1_1") (pintype "passive"))
    )
    (net (code "39") (name "/VU_In") (class "Default")
      (node (ref "C28") (pin "2") (pinfunction "2_2") (pintype "passive"))
      (node (ref "R82") (pin "1") (pinfunction "1_1") (pintype "passive"))
      (node (ref "R82") (pin "2") (pinfunction "2_2") (pintype "passive"))
      (node (ref "R83") (pin "2") (pinfunction "2_2") (pintype "passive"))
      (node (ref "R91") (pin "1") (pinfunction "1_1") (pintype "passive"))
    )
    (net (code "40") (name "Masse") (class "Default")
      (node (ref "C1") (pin "1") (pinfunction "1_1") (pintype "passive"))
      (node (ref "C3") (pin "1") (pinfunction "1_1") (pintype "passive"))
      (node (ref "C36") (pin "1") (pinfunction "1_1") (pintype "passive"))
      (node (ref "C38") (pin "1") (pinfunction "1_1") (pintype "passive"))
      (node (ref "C39") (pin "1") (pinfunction "1_1") (pintype "passive"))
      (node (ref "C40") (pin "1") (pinfunction "1_1") (pintype "passive"))
      (node (ref "C41") (pin "1") (pinfunction "1_1") (pintype "passive"))
      (node (ref "C42") (pin "1") (pinfunction "1_1") (pintype "passive"))
      (node (ref "C43") (pin "1") (pinfunction "1_1") (pintype "passive"))
      (node (ref "C44") (pin "1") (pinfunction "1_1") (pintype "passive"))
      (node (ref "C45") (pin "1") (pinfunction "1_1") (pintype "passive"))
      (node (ref "C46") (pin "1") (pinfunction "1_1") (pintype "passive"))
      (node (ref "C47") (pin "1") (pinfunction "1_1") (pintype "passive"))
      (node (ref "C49") (pin "1") (pinfunction "1_1") (pintype "passive"))
      (node (ref "C50") (pin "1") (pinfunction "1_1") (pintype "passive"))
      (node (ref "C51") (pin "1") (pinfunction "1_1") (pintype "passive"))
      (node (ref "C52") (pin "1") (pinfunction "1_1") (pintype "passive"))
      (node (ref "C53") (pin "1") (pinfunction "1_1") (pintype "passive"))
      (node (ref "C54") (pin "1") (pinfunction "1_1") (pintype "passive"))
      (node (ref "C55") (pin "1") (pinfunction "1_1") (pintype "passive"))
      (node (ref "C56") (pin "1") (pinfunction "1_1") (pintype "passive"))
      (node (ref "C8") (pin "1") (pinfunction "1_1") (pintype "passive"))
      (node (ref "C9") (pin "1") (pinfunction "1_1") (pintype "passive"))
      (node (ref "D3") (pin "1") (pinfunction "A_1") (pintype "passive"))
      (node (ref "J1") (pin "2") (pinfunction "2_2") (pintype "passive"))
      (node (ref "J10") (pin "2") (pinfunction "2_2") (pintype "passive"))
      (node (ref "J10") (pin "3") (pinfunction "3_3") (pintype "passive"))
      (node (ref "J11") (pin "2") (pinfunction "2_2") (pintype "passive"))
      (node (ref "J12") (pin "2") (pinfunction "2_2") (pintype "passive"))
      (node (ref "J13") (pin "2") (pinfunction "2_2") (pintype "passive"))
      (node (ref "J14") (pin "2") (pinfunction "2_2") (pintype "passive"))
      (node (ref "J2") (pin "2") (pinfunction "2_2") (pintype "passive"))
      (node (ref "J3") (pin "2") (pinfunction "2_2") (pintype "passive"))
      (node (ref "J4") (pin "2") (pinfunction "2_2") (pintype "passive"))
      (node (ref "J5") (pin "2") (pinfunction "2_2") (pintype "passive"))
      (node (ref "J6") (pin "2") (pinfunction "2_2") (pintype "passive"))
      (node (ref "J7") (pin "2") (pinfunction "2_2") (pintype "passive"))
      (node (ref "J8") (pin "2") (pinfunction "2_2") (pintype "passive"))
      (node (ref "J9") (pin "3") (pinfunction "3_3") (pintype "passive"))
      (node (ref "J9") (pin "5") (pinfunction "5_5") (pintype "passive"))
      (node (ref "J9") (pin "9") (pinfunction "9_9") (pintype "passive"))
      (node (ref "Q2") (pin "2") (pinfunction "E_2") (pintype "passive"))
      (node (ref "R100") (pin "2") (pinfunction "2_2") (pintype "passive"))
      (node (ref "R101") (pin "1") (pinfunction "1_1") (pintype "passive"))
      (node (ref "R102") (pin "1") (pinfunction "1_1") (pintype "passive"))
      (node (ref "R103") (pin "1") (pinfunction "1_1") (pintype "passive"))
      (node (ref "R104") (pin "1") (pinfunction "1_1") (pintype "passive"))
      (node (ref "R106") (pin "1") (pinfunction "1_1") (pintype "passive"))
      (node (ref "R107") (pin "2") (pinfunction "2_2") (pintype "passive"))
      (node (ref "R11") (pin "1") (pinfunction "1_1") (pintype "passive"))
      (node (ref "R13") (pin "1") (pinfunction "1_1") (pintype "passive"))
      (node (ref "R14") (pin "1") (pinfunction "1_1") (pintype "passive"))
      (node (ref "R30") (pin "1") (pinfunction "1_1") (pintype "passive"))
      (node (ref "R31") (pin "1") (pinfunction "1_1") (pintype "passive"))
      (node (ref "R34") (pin "1") (pinfunction "1_1") (pintype "passive"))
      (node (ref "R36") (pin "1") (pinfunction "1_1") (pintype "passive"))
      (node (ref "R38") (pin "1") (pinfunction "1_1") (pintype "passive"))
      (node (ref "R39") (pin "1") (pinfunction "1_1") (pintype "passive"))
      (node (ref "R46") (pin "1") (pinfunction "1_1") (pintype "passive"))
      (node (ref "R49") (pin "1") (pinfunction "1_1") (pintype "passive"))
      (node (ref "R52") (pin "1") (pinfunction "1_1") (pintype "passive"))
      (node (ref "R53") (pin "1") (pinfunction "1_1") (pintype "passive"))
      (node (ref "R54") (pin "1") (pinfunction "1_1") (pintype "passive"))
      (node (ref "R55") (pin "1") (pinfunction "1_1") (pintype "passive"))
      (node (ref "R60") (pin "1") (pinfunction "1_1") (pintype "passive"))
      (node (ref "R61") (pin "1") (pinfunction "1_1") (pintype "passive"))
      (node (ref "R62") (pin "1") (pinfunction "1_1") (pintype "passive"))
      (node (ref "R63") (pin "1") (pinfunction "1_1") (pintype "passive"))
      (node (ref "R64") (pin "1") (pinfunction "1_1") (pintype "passive"))
      (node (ref "R65") (pin "1") (pinfunction "1_1") (pintype "passive"))
      (node (ref "R68") (pin "1") (pinfunction "1_1") (pintype "passive"))
      (node (ref "R8") (pin "1") (pinfunction "1_1") (pintype "passive"))
      (node (ref "R80") (pin "1") (pinfunction "1_1") (pintype "passive"))
      (node (ref "R81") (pin "1") (pinfunction "1_1") (pintype "passive"))
      (node (ref "R83") (pin "1") (pinfunction "1_1") (pintype "passive"))
      (node (ref "R84") (pin "1") (pinfunction "1_1") (pintype "passive"))
      (node (ref "R88") (pin "1") (pinfunction "1_1") (pintype "passive"))
      (node (ref "R89") (pin "2") (pinfunction "2_2") (pintype "passive"))
      (node (ref "R90") (pin "1") (pinfunction "1_1") (pintype "passive"))
      (node (ref "R94") (pin "1") (pinfunction "1_1") (pintype "passive"))
      (node (ref "R96") (pin "1") (pinfunction "1_1") (pintype "passive"))
      (node (ref "R97") (pin "2") (pinfunction "2_2") (pintype "passive"))
      (node (ref "R99") (pin "1") (pinfunction "1_1") (pintype "passive"))
      (node (ref "U26") (pin "12") (pinfunction "IN_D+_12") (pintype "input"))
      (node (ref "U27") (pin "12") (pinfunction "IN_D+_12") (pintype "input"))
      (node (ref "U29") (pin "12") (pinfunction "IN_D+_12") (pintype "input"))
      (node (ref "U30") (pin "10") (pinfunction "IN_C+_10") (pintype "input"))
      (node (ref "U30") (pin "12") (pinfunction "IN_D+_12") (pintype "input"))
    )
    (net (code "41") (name "Net-(C4-Pad2)") (class "Default")
      (node (ref "C4") (pin "2") (pinfunction "2_2") (pintype "passive"))
      (node (ref "R7") (pin "1") (pinfunction "1_1") (pintype "passive"))
    )
    (net (code "42") (name "Net-(C6-Pad2)") (class "Default")
      (node (ref "C6") (pin "2") (pinfunction "2_2") (pintype "passive"))
      (node (ref "R10") (pin "1") (pinfunction "1_1") (pintype "passive"))
    )
    (net (code "43") (name "Net-(C7-Pad2)") (class "Default")
      (node (ref "C7") (pin "2") (pinfunction "2_2") (pintype "passive"))
      (node (ref "R23") (pin "2") (pinfunction "2_2") (pintype "passive"))
      (node (ref "R30") (pin "2") (pinfunction "2_2") (pintype "passive"))
    )
    (net (code "44") (name "Net-(C12-Pad2)") (class "Default")
      (node (ref "C12") (pin "2") (pinfunction "2_2") (pintype "passive"))
      (node (ref "R32") (pin "1") (pinfunction "1_1") (pintype "passive"))
    )
    (net (code "45") (name "Net-(C14-Pad2)") (class "Default")
      (node (ref "C14") (pin "2") (pinfunction "2_2") (pintype "passive"))
      (node (ref "R33") (pin "1") (pinfunction "1_1") (pintype "passive"))
    )
    (net (code "46") (name "Net-(C16-Pad2)") (class "Default")
      (node (ref "C16") (pin "2") (pinfunction "2_2") (pintype "passive"))
      (node (ref "R47") (pin "1") (pinfunction "1_1") (pintype "passive"))
      (node (ref "R52") (pin "2") (pinfunction "2_2") (pintype "passive"))
    )
    (net (code "47") (name "Net-(C17-Pad2)") (class "Default")
      (node (ref "C17") (pin "2") (pinfunction "2_2") (pintype "passive"))
      (node (ref "R48") (pin "1") (pinfunction "1_1") (pintype "passive"))
      (node (ref "R53") (pin "2") (pinfunction "2_2") (pintype "passive"))
    )
    (net (code "48") (name "Net-(C18-Pad2)") (class "Default")
      (node (ref "C18") (pin "2") (pinfunction "2_2") (pintype "passive"))
      (node (ref "R50") (pin "1") (pinfunction "1_1") (pintype "passive"))
      (node (ref "R54") (pin "2") (pinfunction "2_2") (pintype "passive"))
    )
    (net (code "49") (name "Net-(C19-Pad2)") (class "Default")
      (node (ref "C19") (pin "2") (pinfunction "2_2") (pintype "passive"))
      (node (ref "R51") (pin "1") (pinfunction "1_1") (pintype "passive"))
      (node (ref "R55") (pin "2") (pinfunction "2_2") (pintype "passive"))
    )
    (net (code "50") (name "Net-(C25-Pad1)") (class "Default")
      (node (ref "C25") (pin "1") (pinfunction "1_1") (pintype "passive"))
      (node (ref "R75") (pin "1") (pinfunction "1_1") (pintype "passive"))
      (node (ref "R76") (pin "2") (pinfunction "2_2") (pintype "passive"))
    )
    (net (code "51") (name "Net-(C30-Pad1)") (class "Default")
      (node (ref "C30") (pin "1") (pinfunction "1_1") (pintype "passive"))
      (node (ref "R85") (pin "2") (pinfunction "2_2") (pintype "passive"))
      (node (ref "R89") (pin "1") (pinfunction "1_1") (pintype "passive"))
    )
    (net (code "52") (name "Net-(C31-Pad2)") (class "Default")
      (node (ref "C31") (pin "2") (pinfunction "2_2") (pintype "passive"))
      (node (ref "R87") (pin "1") (pinfunction "1_1") (pintype "passive"))
      (node (ref "R90") (pin "2") (pinfunction "2_2") (pintype "passive"))
    )
    (net (code "53") (name "Net-(C32-Pad2)") (class "Default")
      (node (ref "C32") (pin "2") (pinfunction "2_2") (pintype "passive"))
      (node (ref "R92") (pin "2") (pinfunction "2_2") (pintype "passive"))
      (node (ref "R94") (pin "2") (pinfunction "2_2") (pintype "passive"))
    )
    (net (code "54") (name "Net-(C34-Pad1)") (class "Default")
      (node (ref "C34") (pin "1") (pinfunction "1_1") (pintype "passive"))
      (node (ref "R100") (pin "1") (pinfunction "1_1") (pintype "passive"))
      (node (ref "R95") (pin "2") (pinfunction "2_2") (pintype "passive"))
    )
    (net (code "55") (name "Net-(C35-Pad2)") (class "Default")
      (node (ref "C35") (pin "2") (pinfunction "2_2") (pintype "passive"))
      (node (ref "R102") (pin "2") (pinfunction "2_2") (pintype "passive"))
      (node (ref "R98") (pin "1") (pinfunction "1_1") (pintype "passive"))
    )
    (net (code "56") (name "Net-(C57-Pad1)") (class "Default")
      (node (ref "C57") (pin "1") (pinfunction "1_1") (pintype "passive"))
      (node (ref "R105") (pin "2") (pinfunction "2_2") (pintype "passive"))
      (node (ref "R107") (pin "1") (pinfunction "1_1") (pintype "passive"))
    )
    (net (code "57") (name "Net-(D1-A)") (class "Default")
      (node (ref "D1") (pin "1") (pinfunction "A_1") (pintype "passive"))
      (node (ref "R79") (pin "2") (pinfunction "2_2") (pintype "passive"))
    )
    (net (code "58") (name "Net-(D2-A)") (class "Default")
      (node (ref "D2") (pin "1") (pinfunction "A_1") (pintype "passive"))
      (node (ref "D3") (pin "2") (pinfunction "K_2") (pintype "passive"))
      (node (ref "R92") (pin "1") (pinfunction "1_1") (pintype "passive"))
    )
    (net (code "59") (name "Net-(D2-K)") (class "Default")
      (node (ref "C36") (pin "2") (pinfunction "2_2") (pintype "passive"))
      (node (ref "D2") (pin "2") (pinfunction "K_2") (pintype "passive"))
      (node (ref "J10") (pin "1") (pinfunction "1_1") (pintype "passive"))
      (node (ref "R97") (pin "1") (pinfunction "1_1") (pintype "passive"))
    )
    (net (code "60") (name "Net-(Q1-B)") (class "Default")
      (node (ref "Q1") (pin "1") (pinfunction "B_1") (pintype "passive"))
      (node (ref "R76") (pin "1") (pinfunction "1_1") (pintype "passive"))
    )
    (net (code "61") (name "Net-(Q1-C)") (class "Default")
      (node (ref "Q1") (pin "3") (pinfunction "C_3") (pintype "passive"))
      (node (ref "R79") (pin "1") (pinfunction "1_1") (pintype "passive"))
    )
    (net (code "62") (name "Net-(Q2-B)") (class "Default")
      (node (ref "Q2") (pin "1") (pinfunction "B_1") (pintype "passive"))
      (node (ref "R82") (pin "3") (pinfunction "3_3") (pintype "passive"))
      (node (ref "R84") (pin "2") (pinfunction "2_2") (pintype "passive"))
    )
    (net (code "63") (name "Net-(Q2-C)") (class "Default")
      (node (ref "Q2") (pin "3") (pinfunction "C_3") (pintype "passive"))
      (node (ref "R72") (pin "1") (pinfunction "1_1") (pintype "passive"))
      (node (ref "R75") (pin "2") (pinfunction "2_2") (pintype "passive"))
    )
    (net (code "64") (name "Net-(R2-Pad1)") (class "Default")
      (node (ref "R2") (pin "1") (pinfunction "1_1") (pintype "passive"))
      (node (ref "R7") (pin "2") (pinfunction "2_2") (pintype "passive"))
    )
    (net (code "65") (name "Net-(R3-Pad3)") (class "Default")
      (node (ref "R3") (pin "3") (pinfunction "3_3") (pintype "passive"))
      (node (ref "R8") (pin "2") (pinfunction "2_2") (pintype "passive"))
    )
    (net (code "66") (name "Net-(R10-Pad2)") (class "Default")
      (node (ref "R10") (pin "2") (pinfunction "2_2") (pintype "passive"))
      (node (ref "R5") (pin "1") (pinfunction "1_1") (pintype "passive"))
    )
    (net (code "67") (name "Net-(R11-Pad2)") (class "Default")
      (node (ref "R11") (pin "2") (pinfunction "2_2") (pintype "passive"))
      (node (ref "R6") (pin "3") (pinfunction "3_3") (pintype "passive"))
    )
    (net (code "68") (name "Net-(R26-Pad1)") (class "Default")
      (node (ref "R26") (pin "1") (pinfunction "1_1") (pintype "passive"))
      (node (ref "R32") (pin "2") (pinfunction "2_2") (pintype "passive"))
    )
    (net (code "69") (name "Net-(R27-Pad3)") (class "Default")
      (node (ref "R27") (pin "3") (pinfunction "3_3") (pintype "passive"))
      (node (ref "R34") (pin "2") (pinfunction "2_2") (pintype "passive"))
    )
    (net (code "70") (name "Net-(R28-Pad1)") (class "Default")
      (node (ref "R28") (pin "1") (pinfunction "1_1") (pintype "passive"))
      (node (ref "R33") (pin "2") (pinfunction "2_2") (pintype "passive"))
    )
    (net (code "71") (name "Net-(R29-Pad3)") (class "Default")
      (node (ref "R29") (pin "3") (pinfunction "3_3") (pintype "passive"))
      (node (ref "R36") (pin "2") (pinfunction "2_2") (pintype "passive"))
    )
    (net (code "72") (name "Net-(R91-Pad3)") (class "Default")
      (node (ref "R91") (pin "3") (pinfunction "3_3") (pintype "passive"))
      (node (ref "R96") (pin "2") (pinfunction "2_2") (pintype "passive"))
    )
    (net (code "73") (name "Net-(U22A-IN_A-)") (class "Default")
      (node (ref "R1") (pin "1") (pinfunction "1_1") (pintype "passive"))
      (node (ref "R9") (pin "2") (pinfunction "2_2") (pintype "passive"))
      (node (ref "U22") (pin "2") (pinfunction "IN_A-_2") (pintype "input"))
    )
    (net (code "74") (name "Net-(U22A-OUT_A)") (class "Default")
      (node (ref "C2") (pin "1") (pinfunction "1_1") (pintype "passive"))
      (node (ref "R1") (pin "2") (pinfunction "2_2") (pintype "passive"))
      (node (ref "R15") (pin "1") (pinfunction "1_1") (pintype "passive"))
      (node (ref "U22") (pin "1") (pinfunction "OUT_A_1") (pintype "output"))
    )
    (net (code "75") (name "Net-(U22B-IN_B-)") (class "Default")
      (node (ref "C4") (pin "1") (pinfunction "1_1") (pintype "passive"))
      (node (ref "U22") (pin "6") (pinfunction "IN_B-_6") (pintype "input"))
      (node (ref "U22") (pin "7") (pinfunction "OUT_B_7") (pintype "output"))
    )
    (net (code "76") (name "Net-(U22C-IN_C-)") (class "Default")
      (node (ref "C16") (pin "1") (pinfunction "1_1") (pintype "passive"))
      (node (ref "U22") (pin "8") (pinfunction "OUT_C_8") (pintype "output"))
      (node (ref "U22") (pin "9") (pinfunction "IN_C-_9") (pintype "input"))
    )
    (net (code "77") (name "Net-(U22D-IN_D-)") (class "Default")
      (node (ref "C20") (pin "1") (pinfunction "1_1") (pintype "passive"))
      (node (ref "U22") (pin "13") (pinfunction "IN_D-_13") (pintype "input"))
      (node (ref "U22") (pin "14") (pinfunction "OUT_D_14") (pintype "output"))
    )
    (net (code "78") (name "Net-(U23A-IN_A-)") (class "Default")
      (node (ref "R12") (pin "2") (pinfunction "2_2") (pintype "passive"))
      (node (ref "R4") (pin "1") (pinfunction "1_1") (pintype "passive"))
      (node (ref "U23") (pin "2") (pinfunction "IN_A-_2") (pintype "input"))
    )
    (net (code "79") (name "Net-(U23A-OUT_A)") (class "Default")
      (node (ref "C5") (pin "1") (pinfunction "1_1") (pintype "passive"))
      (node (ref "R16") (pin "1") (pinfunction "1_1") (pintype "passive"))
      (node (ref "R4") (pin "2") (pinfunction "2_2") (pintype "passive"))
      (node (ref "U23") (pin "1") (pinfunction "OUT_A_1") (pintype "output"))
    )
    (net (code "80") (name "Net-(U23B-IN_B-)") (class "Default")
      (node (ref "C6") (pin "1") (pinfunction "1_1") (pintype "passive"))
      (node (ref "U23") (pin "6") (pinfunction "IN_B-_6") (pintype "input"))
      (node (ref "U23") (pin "7") (pinfunction "OUT_B_7") (pintype "output"))
    )
    (net (code "81") (name "Net-(U23C-IN_C-)") (class "Default")
      (node (ref "C17") (pin "1") (pinfunction "1_1") (pintype "passive"))
      (node (ref "U23") (pin "8") (pinfunction "OUT_C_8") (pintype "output"))
      (node (ref "U23") (pin "9") (pinfunction "IN_C-_9") (pintype "input"))
    )
    (net (code "82") (name "Net-(U23D-IN_D-)") (class "Default")
      (node (ref "C21") (pin "1") (pinfunction "1_1") (pintype "passive"))
      (node (ref "U23") (pin "13") (pinfunction "IN_D-_13") (pintype "input"))
      (node (ref "U23") (pin "14") (pinfunction "OUT_D_14") (pintype "output"))
    )
    (net (code "83") (name "Net-(U24A-IN_A-)") (class "Default")
      (node (ref "R25") (pin "1") (pinfunction "1_1") (pintype "passive"))
      (node (ref "R37") (pin "2") (pinfunction "2_2") (pintype "passive"))
      (node (ref "U24") (pin "2") (pinfunction "IN_A-_2") (pintype "input"))
    )
    (net (code "84") (name "Net-(U24A-OUT_A)") (class "Default")
      (node (ref "C13") (pin "1") (pinfunction "1_1") (pintype "passive"))
      (node (ref "R25") (pin "2") (pinfunction "2_2") (pintype "passive"))
      (node (ref "R43") (pin "1") (pinfunction "1_1") (pintype "passive"))
      (node (ref "U24") (pin "1") (pinfunction "OUT_A_1") (pintype "output"))
    )
    (net (code "85") (name "Net-(U24B-IN_B-)") (class "Default")
      (node (ref "C14") (pin "1") (pinfunction "1_1") (pintype "passive"))
      (node (ref "U24") (pin "6") (pinfunction "IN_B-_6") (pintype "input"))
      (node (ref "U24") (pin "7") (pinfunction "OUT_B_7") (pintype "output"))
    )
    (net (code "86") (name "Net-(U24C-IN_C-)") (class "Default")
      (node (ref "C18") (pin "1") (pinfunction "1_1") (pintype "passive"))
      (node (ref "U24") (pin "8") (pinfunction "OUT_C_8") (pintype "output"))
      (node (ref "U24") (pin "9") (pinfunction "IN_C-_9") (pintype "input"))
    )
    (net (code "87") (name "Net-(U24D-IN_D-)") (class "Default")
      (node (ref "C22") (pin "1") (pinfunction "1_1") (pintype "passive"))
      (node (ref "U24") (pin "13") (pinfunction "IN_D-_13") (pintype "input"))
      (node (ref "U24") (pin "14") (pinfunction "OUT_D_14") (pintype "output"))
    )
    (net (code "88") (name "Net-(U25A-IN_A-)") (class "Default")
      (node (ref "R22") (pin "1") (pinfunction "1_1") (pintype "passive"))
      (node (ref "R35") (pin "2") (pinfunction "2_2") (pintype "passive"))
      (node (ref "U25") (pin "2") (pinfunction "IN_A-_2") (pintype "input"))
    )
    (net (code "89") (name "Net-(U25A-OUT_A)") (class "Default")
      (node (ref "C10") (pin "1") (pinfunction "1_1") (pintype "passive"))
      (node (ref "R22") (pin "2") (pinfunction "2_2") (pintype "passive"))
      (node (ref "R42") (pin "1") (pinfunction "1_1") (pintype "passive"))
      (node (ref "U25") (pin "1") (pinfunction "OUT_A_1") (pintype "output"))
    )
    (net (code "90") (name "Net-(U25B-IN_B-)") (class "Default")
      (node (ref "C12") (pin "1") (pinfunction "1_1") (pintype "passive"))
      (node (ref "U25") (pin "6") (pinfunction "IN_B-_6") (pintype "input"))
      (node (ref "U25") (pin "7") (pinfunction "OUT_B_7") (pintype "output"))
    )
    (net (code "91") (name "Net-(U25C-IN_C-)") (class "Default")
      (node (ref "C19") (pin "1") (pinfunction "1_1") (pintype "passive"))
      (node (ref "U25") (pin "8") (pinfunction "OUT_C_8") (pintype "output"))
      (node (ref "U25") (pin "9") (pinfunction "IN_C-_9") (pintype "input"))
    )
    (net (code "92") (name "Net-(U25D-IN_D-)") (class "Default")
      (node (ref "C24") (pin "1") (pinfunction "1_1") (pintype "passive"))
      (node (ref "U25") (pin "13") (pinfunction "IN_D-_13") (pintype "input"))
      (node (ref "U25") (pin "14") (pinfunction "OUT_D_14") (pintype "output"))
    )
    (net (code "93") (name "Net-(U26A-IN_A+)") (class "Default")
      (node (ref "C27") (pin "2") (pinfunction "2_2") (pintype "passive"))
      (node (ref "R104") (pin "2") (pinfunction "2_2") (pintype "passive"))
      (node (ref "U26") (pin "10") (pinfunction "IN_C+_10") (pintype "input"))
      (node (ref "U26") (pin "3") (pinfunction "IN_A+_3") (pintype "input"))
      (node (ref "U26") (pin "5") (pinfunction "IN_B+_5") (pintype "input"))
    )
    (net (code "94") (name "Net-(U26A-IN_A-)") (class "Default")
      (node (ref "C28") (pin "1") (pinfunction "1_1") (pintype "passive"))
      (node (ref "U26") (pin "1") (pinfunction "OUT_A_1") (pintype "output"))
      (node (ref "U26") (pin "2") (pinfunction "IN_A-_2") (pintype "input"))
    )
    (net (code "95") (name "Net-(U26B-IN_B-)") (class "Default")
      (node (ref "C31") (pin "1") (pinfunction "1_1") (pintype "passive"))
      (node (ref "U26") (pin "6") (pinfunction "IN_B-_6") (pintype "input"))
      (node (ref "U26") (pin "7") (pinfunction "OUT_B_7") (pintype "output"))
    )
    (net (code "96") (name "Net-(U26C-IN_C-)") (class "Default")
      (node (ref "C35") (pin "1") (pinfunction "1_1") (pintype "passive"))
      (node (ref "U26") (pin "8") (pinfunction "OUT_C_8") (pintype "output"))
      (node (ref "U26") (pin "9") (pinfunction "IN_C-_9") (pintype "input"))
    )
    (net (code "97") (name "Net-(U26D-IN_D-)") (class "Default")
      (node (ref "R69") (pin "2") (pinfunction "2_2") (pintype "passive"))
      (node (ref "R70") (pin "1") (pinfunction "1_1") (pintype "passive"))
      (node (ref "R71") (pin "2") (pinfunction "2_2") (pintype "passive"))
      (node (ref "R74") (pin "2") (pinfunction "2_2") (pintype "passive"))
      (node (ref "R78") (pin "2") (pinfunction "2_2") (pintype "passive"))
      (node (ref "U26") (pin "13") (pinfunction "IN_D-_13") (pintype "input"))
    )
    (net (code "98") (name "Net-(U26D-OUT_D)") (class "Default")
      (node (ref "C27") (pin "1") (pinfunction "1_1") (pintype "passive"))
      (node (ref "R70") (pin "2") (pinfunction "2_2") (pintype "passive"))
      (node (ref "U26") (pin "14") (pinfunction "OUT_D_14") (pintype "output"))
    )
    (net (code "99") (name "Net-(U27A-IN_A+)") (class "Default")
      (node (ref "C29") (pin "2") (pinfunction "2_2") (pintype "passive"))
      (node (ref "R88") (pin "2") (pinfunction "2_2") (pintype "passive"))
      (node (ref "U27") (pin "3") (pinfunction "IN_A+_3") (pintype "input"))
    )
    (net (code "100") (name "Net-(U27A-IN_A-)") (class "Default")
      (node (ref "C30") (pin "2") (pinfunction "2_2") (pintype "passive"))
      (node (ref "U27") (pin "1") (pinfunction "OUT_A_1") (pintype "output"))
      (node (ref "U27") (pin "2") (pinfunction "IN_A-_2") (pintype "input"))
    )
    (net (code "101") (name "Net-(U27B-IN_B+)") (class "Default")
      (node (ref "C33") (pin "2") (pinfunction "2_2") (pintype "passive"))
      (node (ref "R99") (pin "2") (pinfunction "2_2") (pintype "passive"))
      (node (ref "U27") (pin "5") (pinfunction "IN_B+_5") (pintype "input"))
    )
    (net (code "102") (name "Net-(U27B-IN_B-)") (class "Default")
      (node (ref "C34") (pin "2") (pinfunction "2_2") (pintype "passive"))
      (node (ref "U27") (pin "6") (pinfunction "IN_B-_6") (pintype "input"))
      (node (ref "U27") (pin "7") (pinfunction "OUT_B_7") (pintype "output"))
    )
    (net (code "103") (name "Net-(U27C-IN_C+)") (class "Default")
      (node (ref "C48") (pin "1") (pinfunction "1_1") (pintype "passive"))
      (node (ref "R106") (pin "2") (pinfunction "2_2") (pintype "passive"))
      (node (ref "U27") (pin "10") (pinfunction "IN_C+_10") (pintype "input"))
    )
    (net (code "104") (name "Net-(U27C-IN_C-)") (class "Default")
      (node (ref "C57") (pin "2") (pinfunction "2_2") (pintype "passive"))
      (node (ref "U27") (pin "8") (pinfunction "OUT_C_8") (pintype "output"))
      (node (ref "U27") (pin "9") (pinfunction "IN_C-_9") (pintype "input"))
    )
    (net (code "105") (name "Net-(U27D-IN_D-)") (class "Default")
      (node (ref "R105") (pin "1") (pinfunction "1_1") (pintype "passive"))
      (node (ref "R85") (pin "1") (pinfunction "1_1") (pintype "passive"))
      (node (ref "R86") (pin "1") (pinfunction "1_1") (pintype "passive"))
      (node (ref "R95") (pin "1") (pinfunction "1_1") (pintype "passive"))
      (node (ref "U27") (pin "13") (pinfunction "IN_D-_13") (pintype "input"))
    )
    (net (code "106") (name "Net-(U27D-OUT_D)") (class "Default")
      (node (ref "C37") (pin "1") (pinfunction "1_1") (pintype "passive"))
      (node (ref "R86") (pin "2") (pinfunction "2_2") (pintype "passive"))
      (node (ref "U27") (pin "14") (pinfunction "OUT_D_14") (pintype "output"))
    )
    (net (code "107") (name "Net-(U28A-IN_A+)") (class "Default")
      (node (ref "C11") (pin "1") (pinfunction "1_1") (pintype "passive"))
      (node (ref "R68") (pin "2") (pinfunction "2_2") (pintype "passive"))
      (node (ref "U28") (pin "12") (pinfunction "IN_D+_12") (pintype "input"))
      (node (ref "U28") (pin "3") (pinfunction "IN_A+_3") (pintype "input"))
      (node (ref "U29") (pin "3") (pinfunction "IN_A+_3") (pintype "input"))
    )
    (net (code "108") (name "Net-(U28A-IN_A-)") (class "Default")
      (node (ref "R44") (pin "1") (pinfunction "1_1") (pintype "passive"))
      (node (ref "R44") (pin "2") (pinfunction "2_2") (pintype "passive"))
      (node (ref "R45") (pin "1") (pinfunction "1_1") (pintype "passive"))
      (node (ref "S2") (pin "2") (pinfunction "2_2") (pintype "passive"))
      (node (ref "U28") (pin "2") (pinfunction "IN_A-_2") (pintype "input"))
    )
    (net (code "109") (name "Net-(U28A-OUT_A)") (class "Default")
      (node (ref "R41") (pin "1") (pinfunction "1_1") (pintype "passive"))
      (node (ref "R44") (pin "3") (pinfunction "3_3") (pintype "passive"))
      (node (ref "S2") (pin "3") (pinfunction "3_3") (pintype "passive"))
      (node (ref "U28") (pin "1") (pinfunction "OUT_A_1") (pintype "output"))
    )
    (net (code "110") (name "Net-(U28B-IN_B+)") (class "Default")
      (node (ref "R45") (pin "2") (pinfunction "2_2") (pintype "passive"))
      (node (ref "R49") (pin "2") (pinfunction "2_2") (pintype "passive"))
      (node (ref "U28") (pin "5") (pinfunction "IN_B+_5") (pintype "input"))
    )
    (net (code "111") (name "Net-(U28B-IN_B-)") (class "Default")
      (node (ref "R40") (pin "1") (pinfunction "1_1") (pintype "passive"))
      (node (ref "R41") (pin "2") (pinfunction "2_2") (pintype "passive"))
      (node (ref "U28") (pin "6") (pinfunction "IN_B-_6") (pintype "input"))
    )
    (net (code "112") (name "Net-(U28B-OUT_B)") (class "Default")
      (node (ref "C15") (pin "1") (pinfunction "1_1") (pintype "passive"))
      (node (ref "R40") (pin "2") (pinfunction "2_2") (pintype "passive"))
      (node (ref "U28") (pin "7") (pinfunction "OUT_B_7") (pintype "output"))
    )
    (net (code "113") (name "Net-(U28C-IN_C+)") (class "Default")
      (node (ref "R59") (pin "2") (pinfunction "2_2") (pintype "passive"))
      (node (ref "R65") (pin "2") (pinfunction "2_2") (pintype "passive"))
      (node (ref "U28") (pin "10") (pinfunction "IN_C+_10") (pintype "input"))
    )
    (net (code "114") (name "Net-(U28C-IN_C-)") (class "Default")
      (node (ref "R56") (pin "1") (pinfunction "1_1") (pintype "passive"))
      (node (ref "R57") (pin "2") (pinfunction "2_2") (pintype "passive"))
      (node (ref "U28") (pin "9") (pinfunction "IN_C-_9") (pintype "input"))
    )
    (net (code "115") (name "Net-(U28C-OUT_C)") (class "Default")
      (node (ref "C23") (pin "1") (pinfunction "1_1") (pintype "passive"))
      (node (ref "R56") (pin "2") (pinfunction "2_2") (pintype "passive"))
      (node (ref "U28") (pin "8") (pinfunction "OUT_C_8") (pintype "output"))
    )
    (net (code "116") (name "Net-(U28D-IN_D-)") (class "Default")
      (node (ref "R58") (pin "2") (pinfunction "2_2") (pintype "passive"))
      (node (ref "R58") (pin "3") (pinfunction "3_3") (pintype "passive"))
      (node (ref "R59") (pin "1") (pinfunction "1_1") (pintype "passive"))
      (node (ref "S3") (pin "2") (pinfunction "2_2") (pintype "passive"))
      (node (ref "U28") (pin "13") (pinfunction "IN_D-_13") (pintype "input"))
    )
    (net (code "117") (name "Net-(U28D-OUT_D)") (class "Default")
      (node (ref "R57") (pin "1") (pinfunction "1_1") (pintype "passive"))
      (node (ref "R58") (pin "1") (pinfunction "1_1") (pintype "passive"))
      (node (ref "S3") (pin "1") (pinfunction "1_1") (pintype "passive"))
      (node (ref "U28") (pin "14") (pinfunction "OUT_D_14") (pintype "output"))
    )
    (net (code "118") (name "Net-(U29A-IN_A-)") (class "Default")
      (node (ref "R73") (pin "1") (pinfunction "1_1") (pintype "passive"))
      (node (ref "R73") (pin "2") (pinfunction "2_2") (pintype "passive"))
      (node (ref "R77") (pin "1") (pinfunction "1_1") (pintype "passive"))
      (node (ref "S4") (pin "2") (pinfunction "2_2") (pintype "passive"))
      (node (ref "U29") (pin "2") (pinfunction "IN_A-_2") (pintype "input"))
    )
    (net (code "119") (name "Net-(U29A-OUT_A)") (class "Default")
      (node (ref "R67") (pin "1") (pinfunction "1_1") (pintype "passive"))
      (node (ref "R73") (pin "3") (pinfunction "3_3") (pintype "passive"))
      (node (ref "S4") (pin "3") (pinfunction "3_3") (pintype "passive"))
      (node (ref "U29") (pin "1") (pinfunction "OUT_A_1") (pintype "output"))
    )
    (net (code "120") (name "Net-(U29B-IN_B+)") (class "Default")
      (node (ref "R77") (pin "2") (pinfunction "2_2") (pintype "passive"))
      (node (ref "R81") (pin "2") (pinfunction "2_2") (pintype "passive"))
      (node (ref "U29") (pin "5") (pinfunction "IN_B+_5") (pintype "input"))
    )
    (net (code "121") (name "Net-(U29B-IN_B-)") (class "Default")
      (node (ref "R66") (pin "1") (pinfunction "1_1") (pintype "passive"))
      (node (ref "R67") (pin "2") (pinfunction "2_2") (pintype "passive"))
      (node (ref "U29") (pin "6") (pinfunction "IN_B-_6") (pintype "input"))
    )
    (net (code "122") (name "Net-(U29B-OUT_B)") (class "Default")
      (node (ref "C26") (pin "1") (pinfunction "1_1") (pintype "passive"))
      (node (ref "R66") (pin "2") (pinfunction "2_2") (pintype "passive"))
      (node (ref "U29") (pin "7") (pinfunction "OUT_B_7") (pintype "output"))
    )
    (net (code "123") (name "Net-(U29C-IN_C+)") (class "Default")
      (node (ref "R91") (pin "2") (pinfunction "2_2") (pintype "passive"))
      (node (ref "U29") (pin "10") (pinfunction "IN_C+_10") (pintype "input"))
    )
    (net (code "124") (name "Net-(U29C-IN_C-)") (class "Default")
      (node (ref "R103") (pin "2") (pinfunction "2_2") (pintype "passive"))
      (node (ref "R93") (pin "1") (pinfunction "1_1") (pintype "passive"))
      (node (ref "U29") (pin "9") (pinfunction "IN_C-_9") (pintype "input"))
    )
    (net (code "125") (name "Net-(U29C-OUT_C)") (class "Default")
      (node (ref "C32") (pin "1") (pinfunction "1_1") (pintype "passive"))
      (node (ref "R93") (pin "2") (pinfunction "2_2") (pintype "passive"))
      (node (ref "U29") (pin "8") (pinfunction "OUT_C_8") (pintype "output"))
    )
    (net (code "126") (name "Net-(U29D-IN_D-)") (class "Default")
      (node (ref "U29") (pin "13") (pinfunction "IN_D-_13") (pintype "input"))
      (node (ref "U29") (pin "14") (pinfunction "OUT_D_14") (pintype "output"))
    )
    (net (code "127") (name "Net-(U30A-IN_A-)") (class "Default")
      (node (ref "R21") (pin "1") (pinfunction "1_1") (pintype "passive"))
      (node (ref "R24") (pin "1") (pinfunction "1_1") (pintype "passive"))
      (node (ref "S1") (pin "2") (pinfunction "2_2") (pintype "passive"))
      (node (ref "U30") (pin "2") (pinfunction "IN_A-_2") (pintype "input"))
    )
    (net (code "128") (name "Net-(U30A-OUT_A)") (class "Default")
      (node (ref "R17") (pin "1") (pinfunction "1_1") (pintype "passive"))
      (node (ref "R21") (pin "2") (pinfunction "2_2") (pintype "passive"))
      (node (ref "S1") (pin "3") (pinfunction "3_3") (pintype "passive"))
      (node (ref "U30") (pin "1") (pinfunction "OUT_A_1") (pintype "output"))
    )
    (net (code "129") (name "Net-(U30B-IN_B+)") (class "Default")
      (node (ref "R24") (pin "2") (pinfunction "2_2") (pintype "passive"))
      (node (ref "R31") (pin "2") (pinfunction "2_2") (pintype "passive"))
      (node (ref "U30") (pin "5") (pinfunction "IN_B+_5") (pintype "input"))
    )
    (net (code "130") (name "Net-(U30B-IN_B-)") (class "Default")
      (node (ref "R17") (pin "2") (pinfunction "2_2") (pintype "passive"))
      (node (ref "R18") (pin "1") (pinfunction "1_1") (pintype "passive"))
      (node (ref "U30") (pin "6") (pinfunction "IN_B-_6") (pintype "input"))
    )
    (net (code "131") (name "Net-(U30B-OUT_B)") (class "Default")
      (node (ref "C7") (pin "1") (pinfunction "1_1") (pintype "passive"))
      (node (ref "R18") (pin "2") (pinfunction "2_2") (pintype "passive"))
      (node (ref "U30") (pin "7") (pinfunction "OUT_B_7") (pintype "output"))
    )
    (net (code "132") (name "Net-(U30C-IN_C-)") (class "Default")
      (node (ref "R19") (pin "1") (pinfunction "1_1") (pintype "passive"))
      (node (ref "R20") (pin "1") (pinfunction "1_1") (pintype "passive"))
      (node (ref "R23") (pin "1") (pinfunction "1_1") (pintype "passive"))
      (node (ref "U30") (pin "9") (pinfunction "IN_C-_9") (pintype "input"))
    )
    (net (code "133") (name "Net-(U30C-OUT_C)") (class "Default")
      (node (ref "C11") (pin "2") (pinfunction "2_2") (pintype "passive"))
      (node (ref "R20") (pin "2") (pinfunction "2_2") (pintype "passive"))
      (node (ref "U30") (pin "8") (pinfunction "OUT_C_8") (pintype "output"))
    )
    (net (code "134") (name "Net-(U30D-IN_D-)") (class "Default")
      (node (ref "U30") (pin "13") (pinfunction "IN_D-_13") (pintype "input"))
      (node (ref "U30") (pin "14") (pinfunction "OUT_D_14") (pintype "output"))
    )
    (net (code "135") (name "unconnected-(J9-Pad1)") (class "Default")
      (node (ref "J9") (pin "1") (pinfunction "1_1") (pintype "passive+no_connect"))
    )
    (net (code "136") (name "unconnected-(S1-Pad1)") (class "Default")
      (node (ref "S1") (pin "1") (pinfunction "1_1") (pintype "passive"))
    )
    (net (code "137") (name "unconnected-(S2-Pad1)") (class "Default")
      (node (ref "S2") (pin "1") (pinfunction "1_1") (pintype "passive"))
    )
    (net (code "138") (name "unconnected-(S3-Pad3)") (class "Default")
      (node (ref "S3") (pin "3") (pinfunction "3_3") (pintype "passive"))
    )
    (net (code "139") (name "unconnected-(S4-Pad1)") (class "Default")
      (node (ref "S4") (pin "1") (pinfunction "1_1") (pintype "passive"))
    )
  )
)
